# tactile.net
KiCad netlist of a schematic drawn in EAGLE
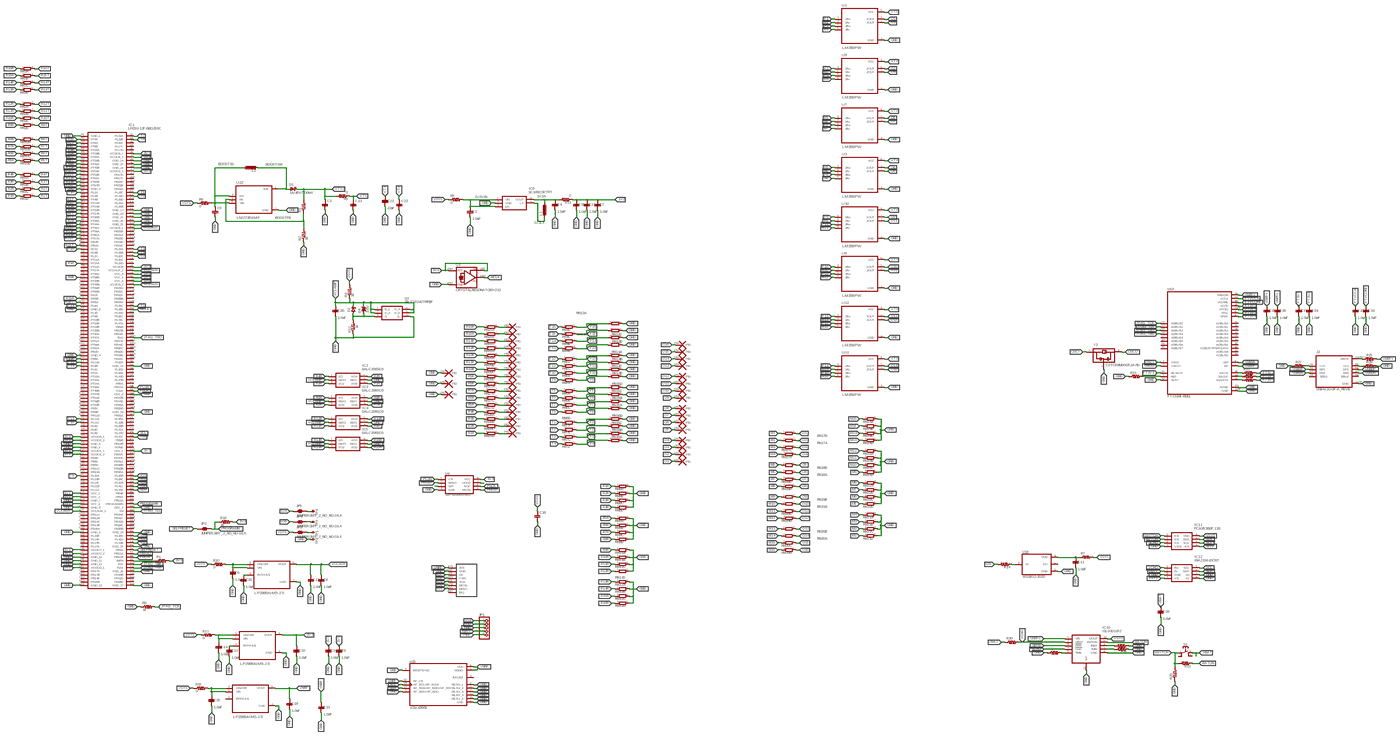
[diagram p0: schematic, sheet 1, overview]
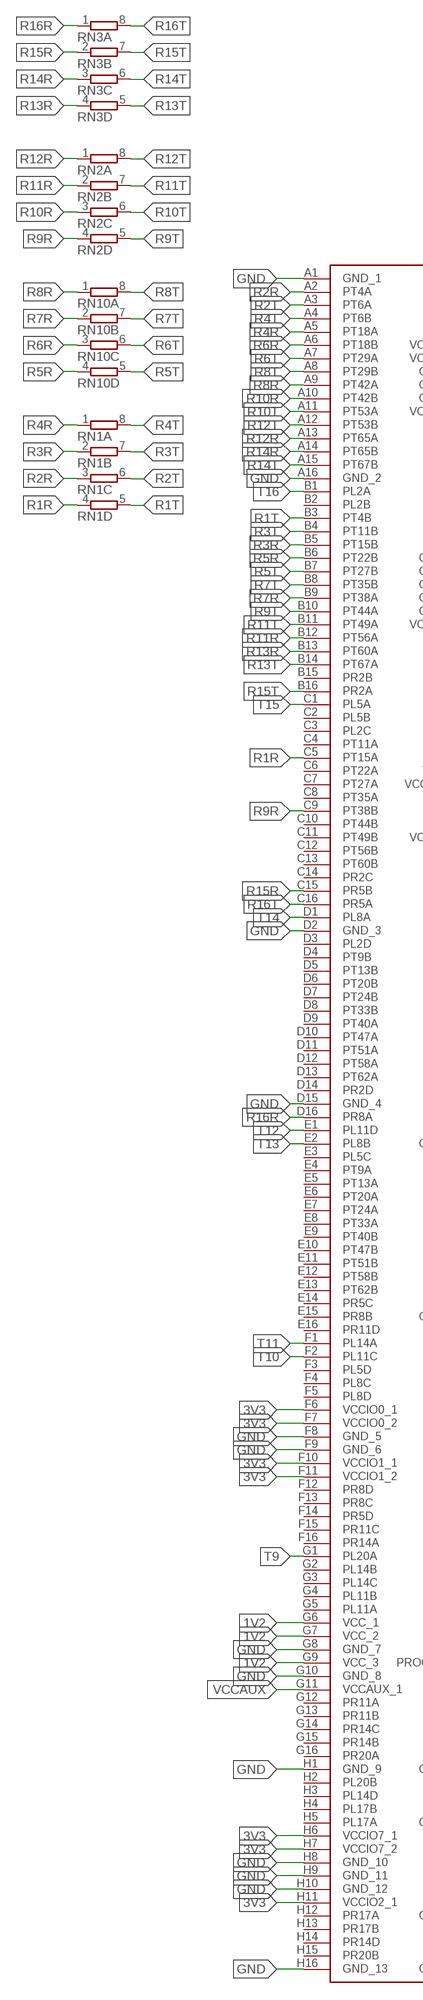
[diagram p1: schematic, sheet 1, part 1 of 4]
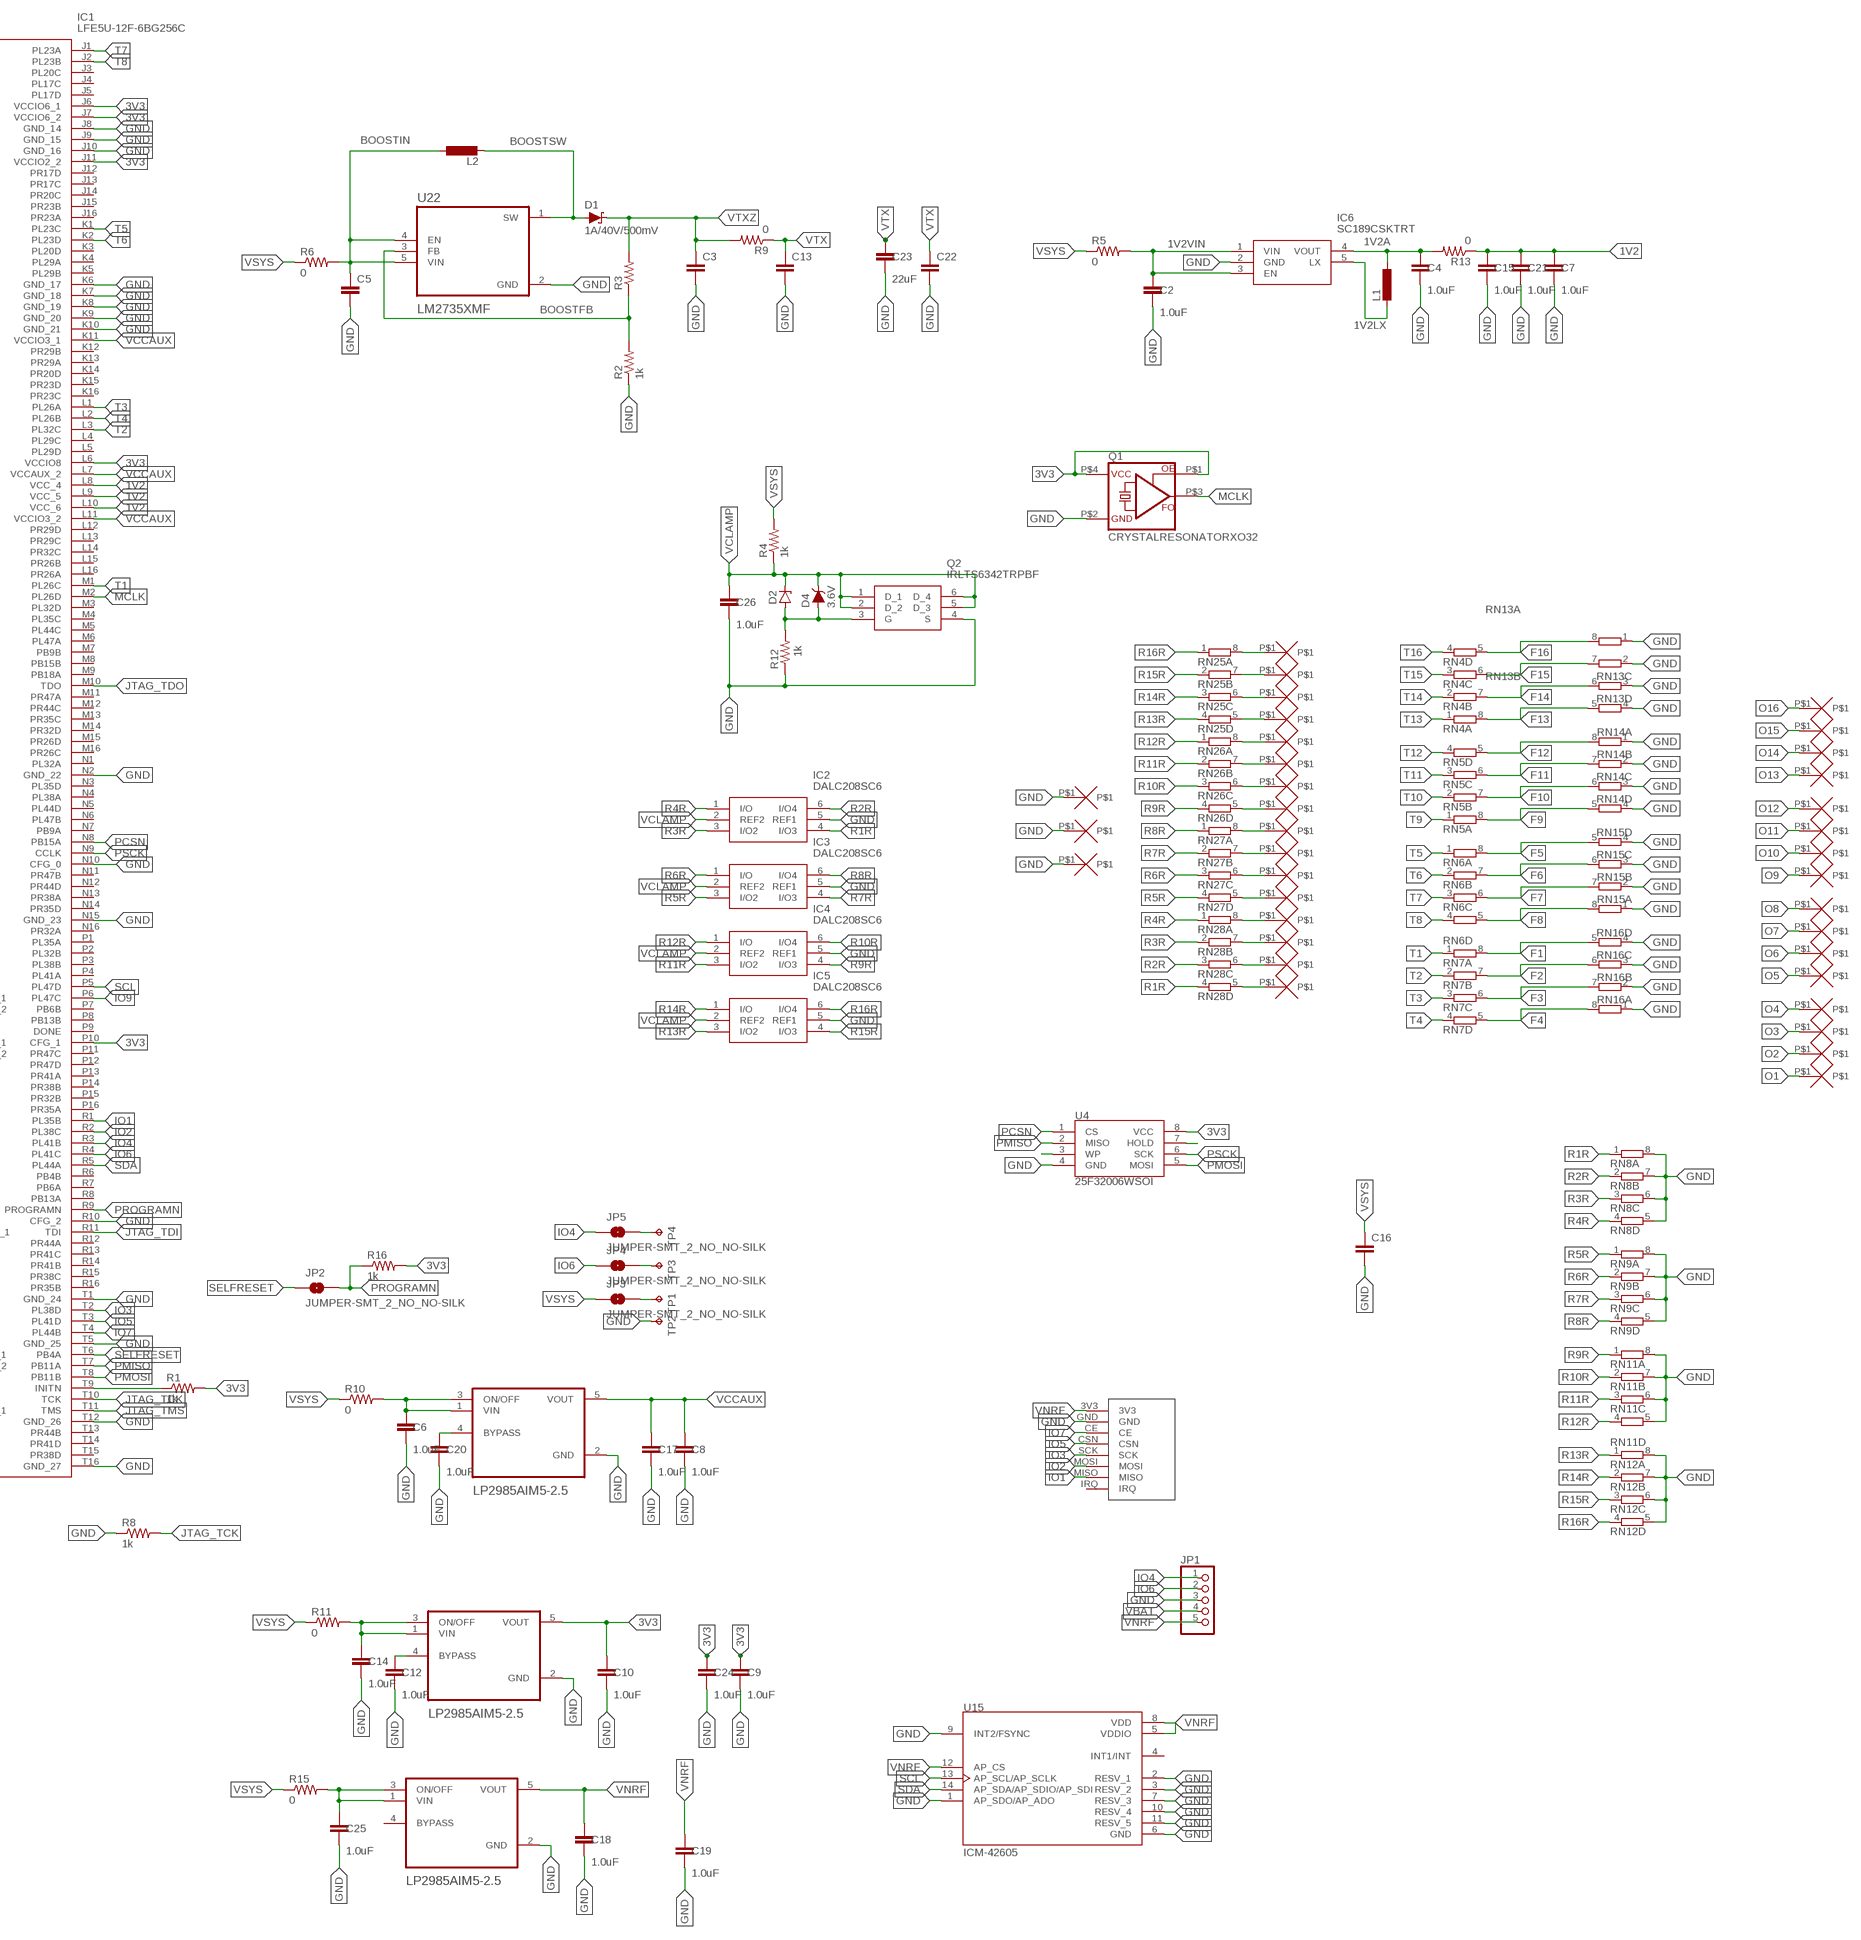
[diagram p2: schematic, sheet 1, part 2 of 4]
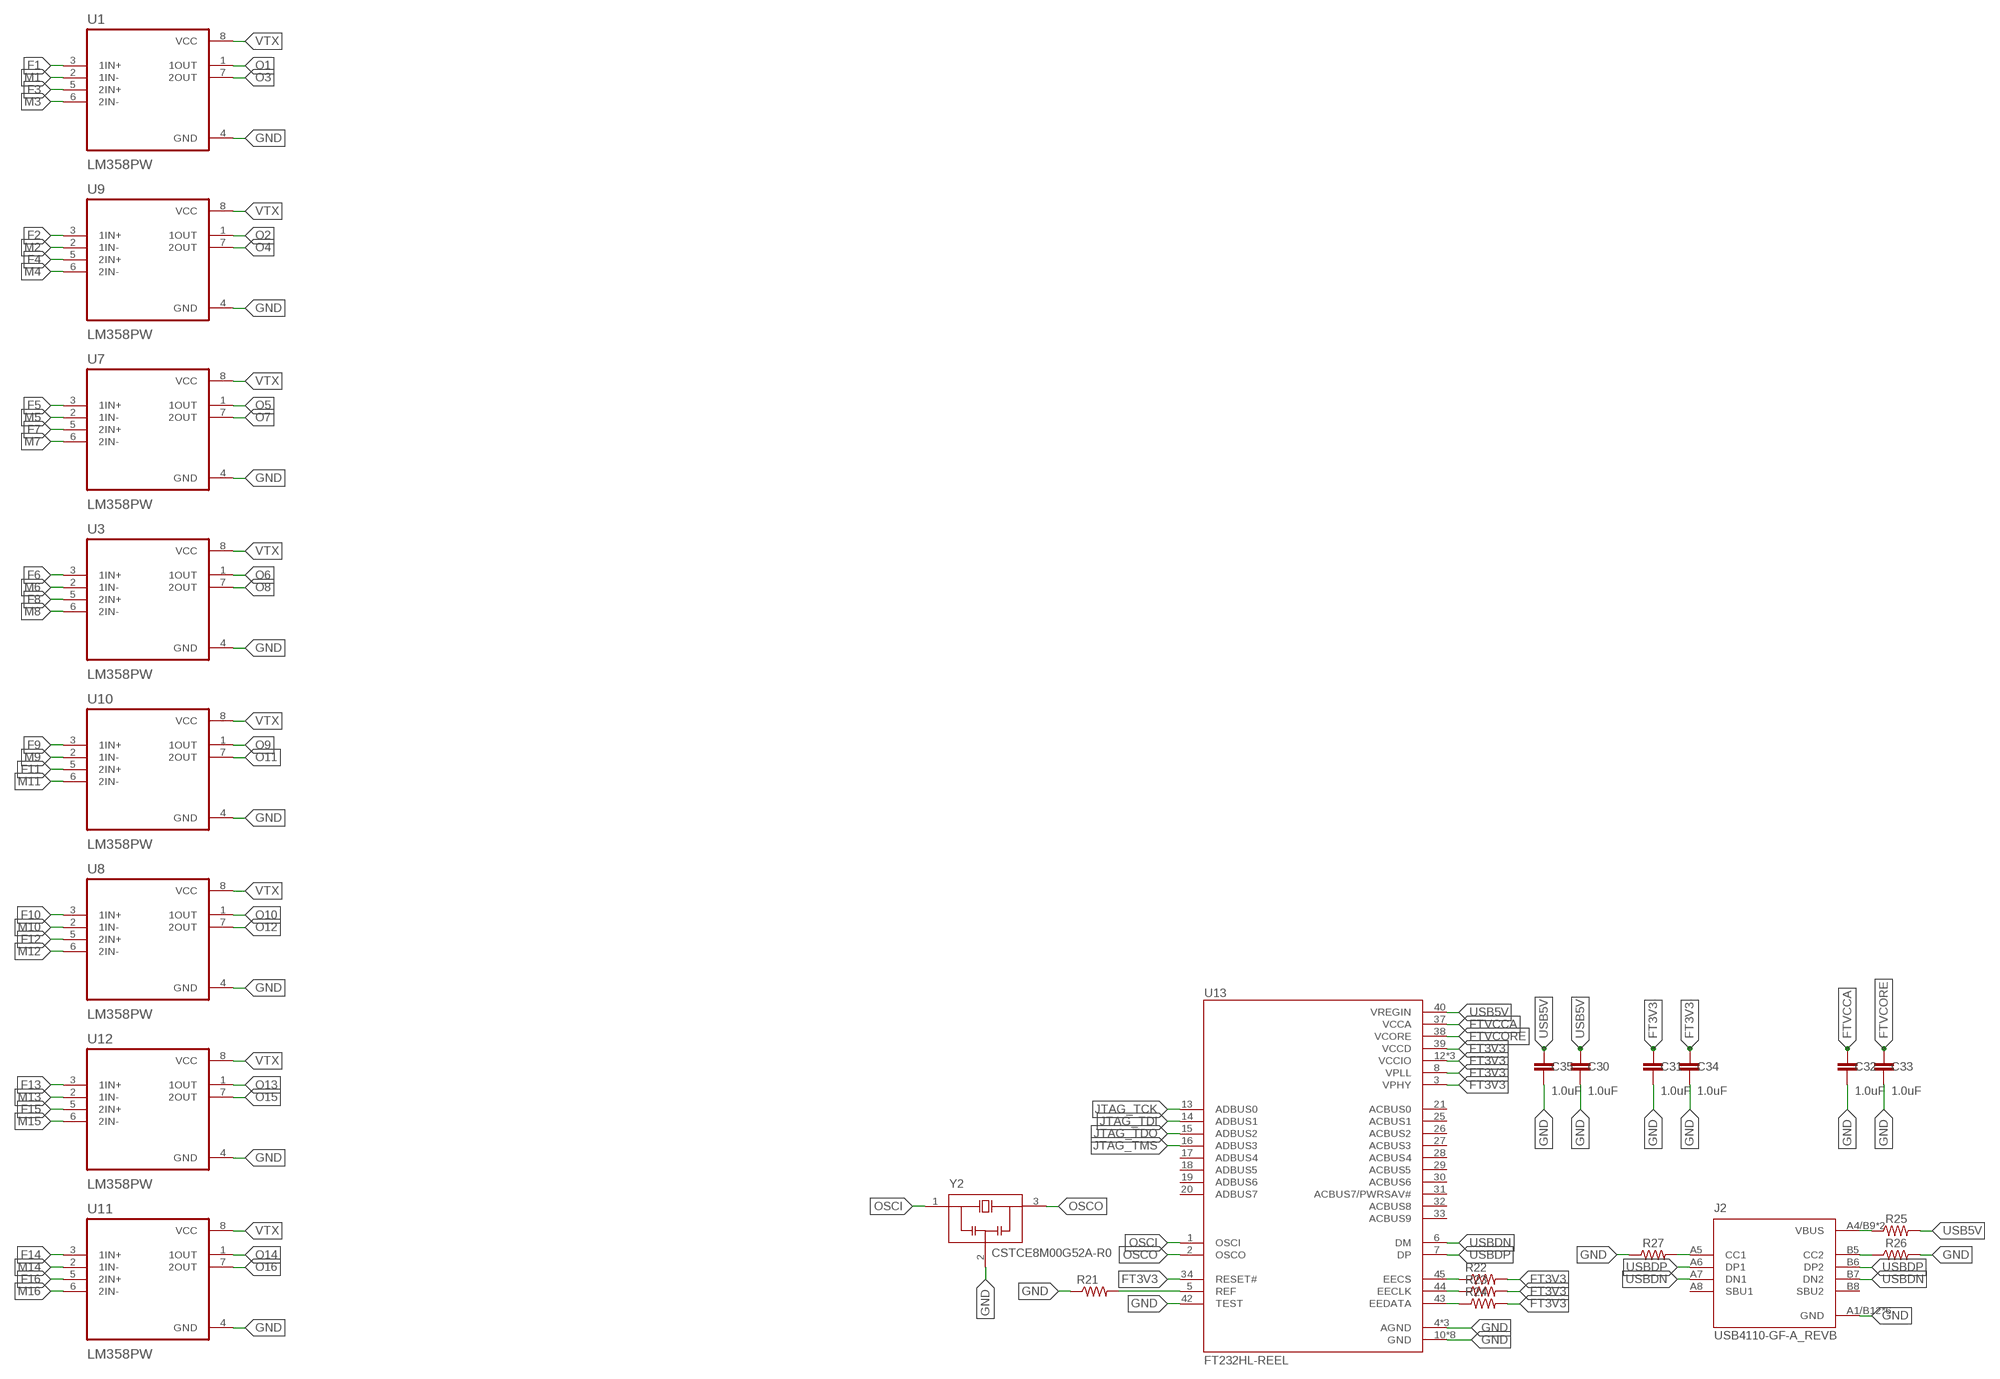
[diagram p3: schematic, sheet 1, part 3 of 4]
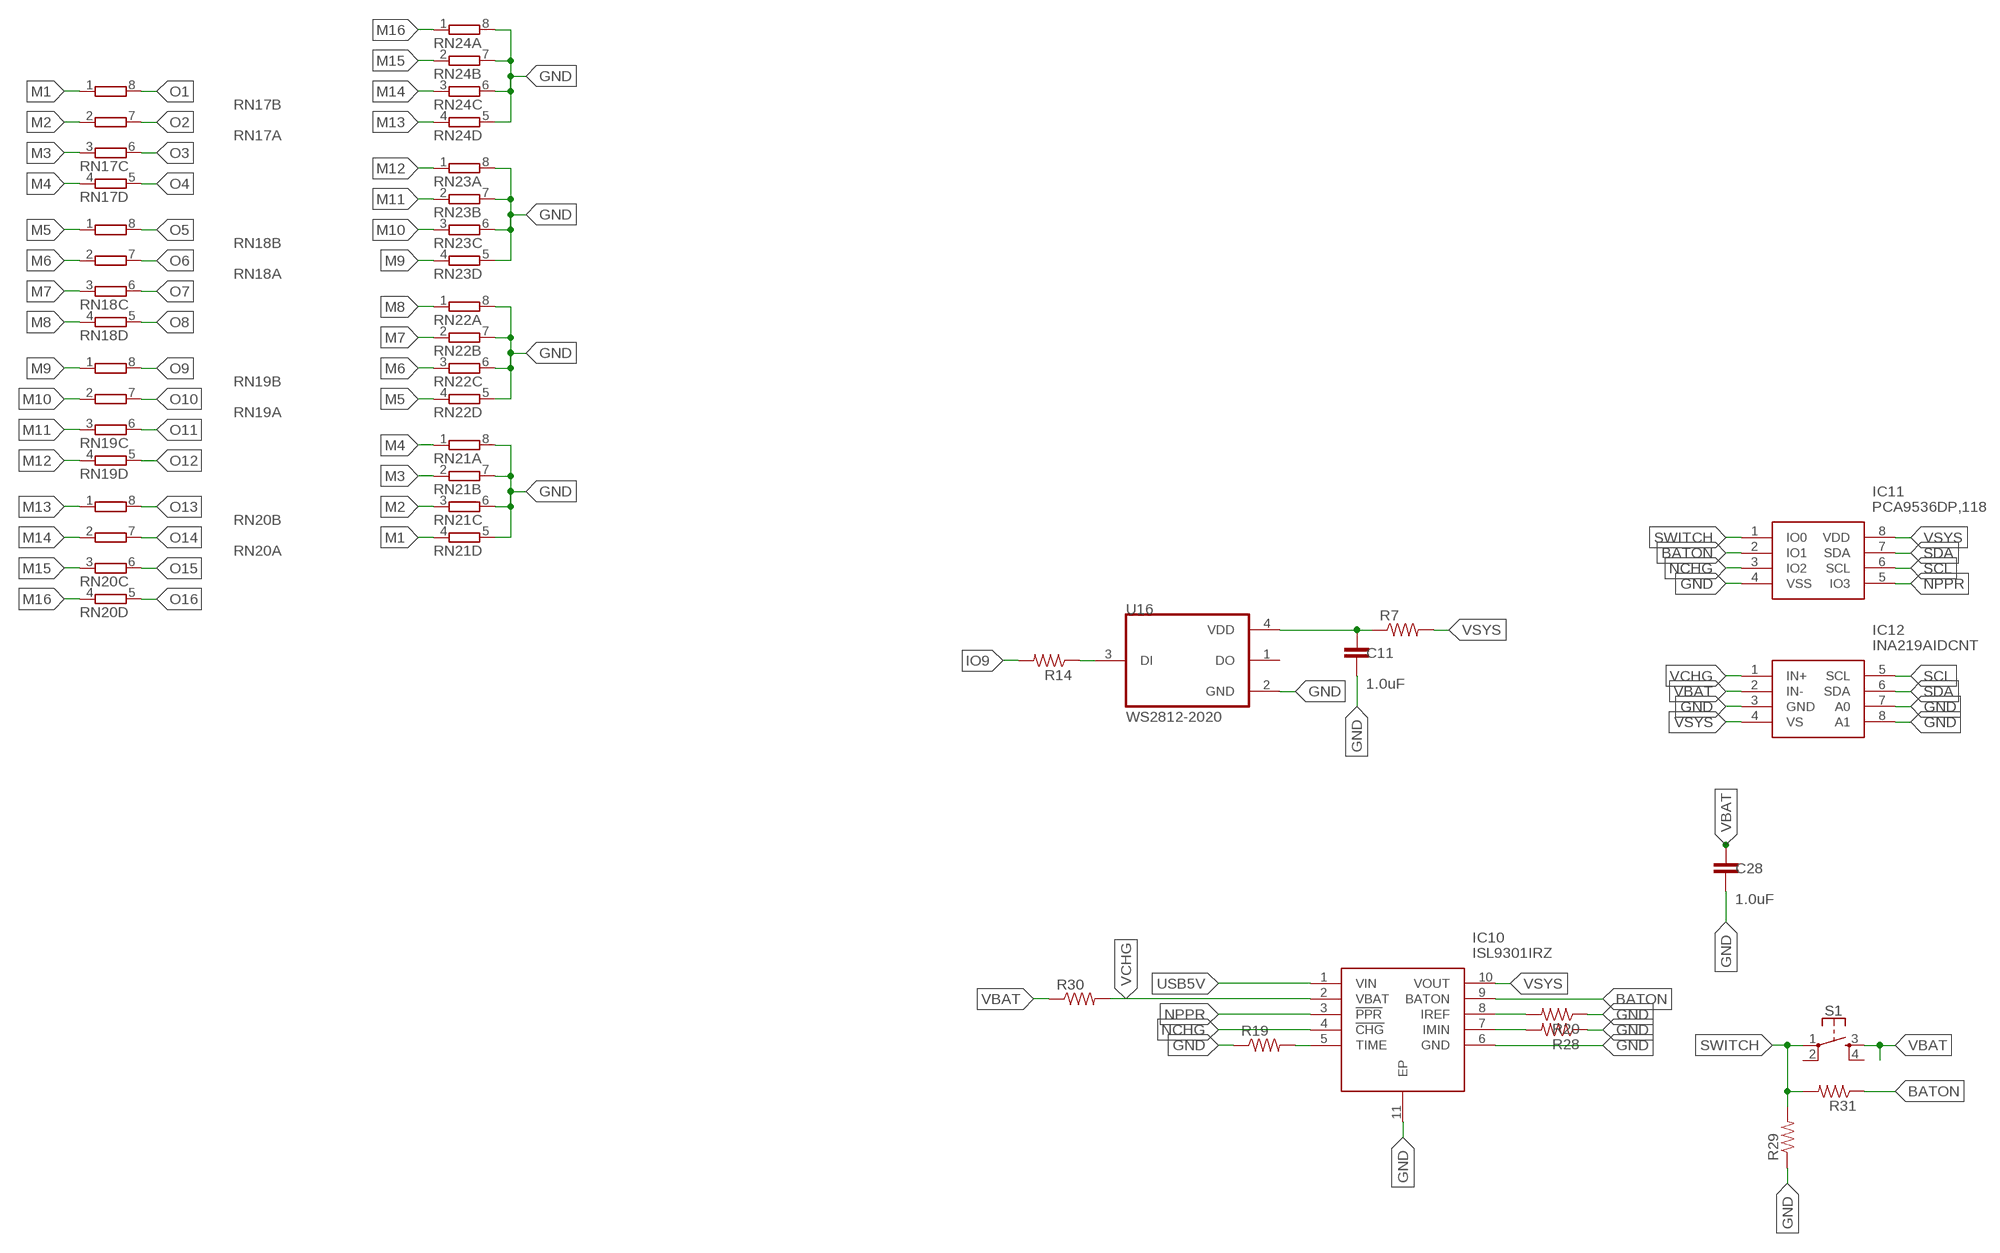
[diagram p4: schematic, sheet 1, part 4 of 4]

(export (version "E")
  (design (tool "Eeschema 10.0.6"))
  (components
    (comp (ref "C2")
      (value "1.0uF")
      (footprint "eagle-import:0603")
      (libsource (lib "eagle-import") (part "1.0UF-0603-16V-10%"))
    )
    (comp (ref "C3")
      (value "C-EUC0805")
      (footprint "eagle-import:C0805")
      (libsource (lib "eagle-import") (part "C-EUC0805"))
    )
    (comp (ref "C4")
      (value "1.0uF")
      (footprint "eagle-import:0603")
      (libsource (lib "eagle-import") (part "1.0UF-0603-16V-10%"))
    )
    (comp (ref "C5")
      (value "C-EUC0805")
      (footprint "eagle-import:C0805")
      (libsource (lib "eagle-import") (part "C-EUC0805"))
    )
    (comp (ref "C6")
      (value "1.0uF")
      (footprint "eagle-import:0603")
      (libsource (lib "eagle-import") (part "1.0UF-0603-16V-10%"))
    )
    (comp (ref "C7")
      (value "1.0uF")
      (footprint "eagle-import:0603")
      (libsource (lib "eagle-import") (part "1.0UF-0603-16V-10%"))
    )
    (comp (ref "C8")
      (value "1.0uF")
      (footprint "eagle-import:0603")
      (libsource (lib "eagle-import") (part "1.0UF-0603-16V-10%"))
    )
    (comp (ref "C9")
      (value "1.0uF")
      (footprint "eagle-import:0603")
      (libsource (lib "eagle-import") (part "1.0UF-0603-16V-10%"))
    )
    (comp (ref "C10")
      (value "1.0uF")
      (footprint "eagle-import:0603")
      (libsource (lib "eagle-import") (part "1.0UF-0603-16V-10%"))
    )
    (comp (ref "C11")
      (value "1.0uF")
      (footprint "eagle-import:0603")
      (libsource (lib "eagle-import") (part "1.0UF-0603-16V-10%"))
    )
    (comp (ref "C12")
      (value "1.0uF")
      (footprint "eagle-import:0603")
      (libsource (lib "eagle-import") (part "1.0UF-0603-16V-10%"))
    )
    (comp (ref "C13")
      (value "C-EUC0805")
      (footprint "eagle-import:C0805")
      (libsource (lib "eagle-import") (part "C-EUC0805"))
    )
    (comp (ref "C14")
      (value "1.0uF")
      (footprint "eagle-import:0603")
      (libsource (lib "eagle-import") (part "1.0UF-0603-16V-10%"))
    )
    (comp (ref "C15")
      (value "1.0uF")
      (footprint "eagle-import:0603")
      (libsource (lib "eagle-import") (part "1.0UF-0603-16V-10%"))
    )
    (comp (ref "C16")
      (value "C-EUC1812")
      (footprint "eagle-import:C1812")
      (libsource (lib "eagle-import") (part "C-EUC1812"))
    )
    (comp (ref "C17")
      (value "1.0uF")
      (footprint "eagle-import:0603")
      (libsource (lib "eagle-import") (part "1.0UF-0603-16V-10%"))
    )
    (comp (ref "C18")
      (value "1.0uF")
      (footprint "eagle-import:0603")
      (libsource (lib "eagle-import") (part "1.0UF-0603-16V-10%"))
    )
    (comp (ref "C19")
      (value "1.0uF")
      (footprint "eagle-import:0603")
      (libsource (lib "eagle-import") (part "1.0UF-0603-16V-10%"))
    )
    (comp (ref "C20")
      (value "1.0uF")
      (footprint "eagle-import:0603")
      (libsource (lib "eagle-import") (part "1.0UF-0603-16V-10%"))
    )
    (comp (ref "C21")
      (value "1.0uF")
      (footprint "eagle-import:0603")
      (libsource (lib "eagle-import") (part "1.0UF-0603-16V-10%"))
    )
    (comp (ref "C22")
      (value "C-EUC0805")
      (footprint "eagle-import:C0805")
      (libsource (lib "eagle-import") (part "C-EUC0805"))
    )
    (comp (ref "C23")
      (value "22uF")
      (footprint "eagle-import:0805")
      (libsource (lib "eagle-import") (part "22UF-0805-16V-20%"))
    )
    (comp (ref "C24")
      (value "1.0uF")
      (footprint "eagle-import:0603")
      (libsource (lib "eagle-import") (part "1.0UF-0603-16V-10%"))
    )
    (comp (ref "C25")
      (value "1.0uF")
      (footprint "eagle-import:0603")
      (libsource (lib "eagle-import") (part "1.0UF-0603-16V-10%"))
    )
    (comp (ref "C26")
      (value "1.0uF")
      (footprint "eagle-import:0603")
      (libsource (lib "eagle-import") (part "1.0UF-0603-16V-10%"))
    )
    (comp (ref "C28")
      (value "1.0uF")
      (footprint "eagle-import:0603")
      (libsource (lib "eagle-import") (part "1.0UF-0603-16V-10%"))
    )
    (comp (ref "C30")
      (value "1.0uF")
      (footprint "eagle-import:1206")
      (libsource (lib "eagle-import") (part "1.0UF-1206-50V-10%"))
    )
    (comp (ref "C31")
      (value "1.0uF")
      (footprint "eagle-import:0603")
      (libsource (lib "eagle-import") (part "1.0UF-0603-16V-10%"))
    )
    (comp (ref "C32")
      (value "1.0uF")
      (footprint "eagle-import:0603")
      (libsource (lib "eagle-import") (part "1.0UF-0603-16V-10%"))
    )
    (comp (ref "C33")
      (value "1.0uF")
      (footprint "eagle-import:0603")
      (libsource (lib "eagle-import") (part "1.0UF-0603-16V-10%"))
    )
    (comp (ref "C34")
      (value "1.0uF")
      (footprint "eagle-import:0603")
      (libsource (lib "eagle-import") (part "1.0UF-0603-16V-10%"))
    )
    (comp (ref "C35")
      (value "1.0uF")
      (footprint "eagle-import:0603")
      (libsource (lib "eagle-import") (part "1.0UF-0603-16V-10%"))
    )
    (comp (ref "D1")
      (value "1A/40V/500mV")
      (footprint "eagle-import:SMA-DIODE")
      (libsource (lib "eagle-import") (part "DIODE-SCHOTTKY-SS14"))
    )
    (comp (ref "D2")
      (value "ZENER-DIODESOT23")
      (footprint "eagle-import:SOT23")
      (libsource (lib "eagle-import") (part "ZENER-DIODESOT23"))
    )
    (comp (ref "D4")
      (value "3.6V")
      (footprint "eagle-import:SOD-323")
      (libsource (lib "eagle-import") (part "DIODE-ZENER-BZT52C3V6S"))
    )
    (comp (ref "IC1")
      (value "LFE5U-12F-6BG256C")
      (footprint "eagle-import:BGA256C80P16X16_1400X1400X170")
      (fields (field (name "MF") "Lattice Semiconductor"))
      (libsource (lib "eagle-import") (part "LFE5U-12F-6BG256C"))
    )
    (comp (ref "IC2")
      (value "DALC208SC6")
      (footprint "eagle-import:SOT95P280X145-6N")
      (fields (field (name "MF") "STMicroelectronics"))
      (libsource (lib "eagle-import") (part "DALC208SC6"))
    )
    (comp (ref "IC3")
      (value "DALC208SC6")
      (footprint "eagle-import:SOT95P280X145-6N")
      (fields (field (name "MF") "STMicroelectronics"))
      (libsource (lib "eagle-import") (part "DALC208SC6"))
    )
    (comp (ref "IC4")
      (value "DALC208SC6")
      (footprint "eagle-import:SOT95P280X145-6N")
      (fields (field (name "MF") "STMicroelectronics"))
      (libsource (lib "eagle-import") (part "DALC208SC6"))
    )
    (comp (ref "IC5")
      (value "DALC208SC6")
      (footprint "eagle-import:SOT95P280X145-6N")
      (fields (field (name "MF") "STMicroelectronics"))
      (libsource (lib "eagle-import") (part "DALC208SC6"))
    )
    (comp (ref "IC6")
      (value "SC189CSKTRT")
      (footprint "eagle-import:SOT95P280X145-5N")
      (fields (field (name "MOUSER_PART_NUMBER") "947-SC189CSKTRT"))
      (libsource (lib "eagle-import") (part "SC189CSKTRT"))
    )
    (comp (ref "IC10")
      (value "ISL9301IRZ")
      (footprint "eagle-import:SON50P300X300X90-11N")
      (fields (field (name "MOUSER_PART_NUMBER") "968-ISL9301IRZ"))
      (libsource (lib "eagle-import") (part "ISL9301IRZ"))
    )
    (comp (ref "IC11")
      (value "PCA9536DP,118")
      (footprint "eagle-import:SOP65P490X110-8N")
      (fields (field (name "MOUSER_PART_NUMBER") "771-PCA9536DP-T"))
      (libsource (lib "eagle-import") (part "PCA9536DP,118"))
    )
    (comp (ref "IC12")
      (value "INA219AIDCNT")
      (footprint "eagle-import:SOT65P280X145-8N")
      (fields (field (name "MOUSER_PART_NUMBER") "595-INA219AIDCNT"))
      (libsource (lib "eagle-import") (part "INA219AIDCNT"))
    )
    (comp (ref "J2")
      (value "USB4110-GF-A_REVB")
      (footprint "eagle-import:GCT_USB4110-GF-A_REVB")
      (fields (field (name "MF") "GCT") (field (name "MP") "USB4110-GF-A"))
      (libsource (lib "eagle-import") (part "USB4110-GF-A_REVB"))
    )
    (comp (ref "JP1")
      (value "PINHD-1X5M")
      (footprint "eagle-import:1X05M")
      (libsource (lib "eagle-import") (part "PINHD-1X5M"))
    )
    (comp (ref "JP2")
      (value "JUMPER-SMT_2_NO_NO-SILK")
      (footprint "eagle-import:SMT-JUMPER_2_NO_NO-SILK")
      (libsource (lib "eagle-import") (part "JUMPER-SMT_2_NO_NO-SILK"))
    )
    (comp (ref "JP3")
      (value "JUMPER-SMT_2_NO_NO-SILK")
      (footprint "eagle-import:SMT-JUMPER_2_NO_NO-SILK")
      (libsource (lib "eagle-import") (part "JUMPER-SMT_2_NO_NO-SILK"))
    )
    (comp (ref "JP4")
      (value "JUMPER-SMT_2_NO_NO-SILK")
      (footprint "eagle-import:SMT-JUMPER_2_NO_NO-SILK")
      (libsource (lib "eagle-import") (part "JUMPER-SMT_2_NO_NO-SILK"))
    )
    (comp (ref "JP5")
      (value "JUMPER-SMT_2_NO_NO-SILK")
      (footprint "eagle-import:SMT-JUMPER_2_NO_NO-SILK")
      (libsource (lib "eagle-import") (part "JUMPER-SMT_2_NO_NO-SILK"))
    )
    (comp (ref "L1")
      (value "L-EUL3230M")
      (footprint "eagle-import:L3230M")
      (libsource (lib "eagle-import") (part "L-EUL3230M"))
    )
    (comp (ref "L2")
      (value "L-EUL3225P")
      (footprint "eagle-import:L3225P")
      (libsource (lib "eagle-import") (part "L-EUL3225P"))
    )
    (comp (ref "Q1")
      (value "CRYSTALRESONATORXO32")
      (footprint "eagle-import:XO32")
      (libsource (lib "eagle-import") (part "CRYSTALRESONATORXO32"))
    )
    (comp (ref "Q2")
      (value "IRLTS6342TRPBF")
      (footprint "eagle-import:SOT95P280X145-6N")
      (fields (field (name "MOUSER_PART_NUMBER") "942-IRLTS6342TRPBF"))
      (libsource (lib "eagle-import") (part "IRLTS6342TRPBF"))
    )
    (comp (ref "R1")
      (value "1k")
      (footprint "eagle-import:0603")
      (libsource (lib "eagle-import") (part "1KOHM-0603-1/10W-1%"))
    )
    (comp (ref "R2")
      (value "1k")
      (footprint "eagle-import:0603")
      (libsource (lib "eagle-import") (part "1KOHM-0603-1/10W-1%"))
    )
    (comp (ref "R3")
      (value "1k")
      (footprint "eagle-import:0603")
      (libsource (lib "eagle-import") (part "1KOHM-0603-1/10W-1%"))
    )
    (comp (ref "R4")
      (value "1k")
      (footprint "eagle-import:0603")
      (libsource (lib "eagle-import") (part "1KOHM-0603-1/10W-1%"))
    )
    (comp (ref "R5")
      (value "0")
      (footprint "eagle-import:0603")
      (libsource (lib "eagle-import") (part "0OHM-0603-1/10W"))
    )
    (comp (ref "R6")
      (value "0")
      (footprint "eagle-import:0603")
      (libsource (lib "eagle-import") (part "0OHM-0603-1/10W"))
    )
    (comp (ref "R7")
      (value "RESISTOR0603")
      (footprint "eagle-import:0603")
      (libsource (lib "eagle-import") (part "RESISTOR0603"))
    )
    (comp (ref "R8")
      (value "1k")
      (footprint "eagle-import:0603")
      (libsource (lib "eagle-import") (part "1KOHM-0603-1/10W-1%"))
    )
    (comp (ref "R9")
      (value "0")
      (footprint "eagle-import:0603")
      (libsource (lib "eagle-import") (part "0OHM-0603-1/10W"))
    )
    (comp (ref "R10")
      (value "0")
      (footprint "eagle-import:0603")
      (libsource (lib "eagle-import") (part "0OHM-0603-1/10W"))
    )
    (comp (ref "R11")
      (value "0")
      (footprint "eagle-import:0603")
      (libsource (lib "eagle-import") (part "0OHM-0603-1/10W"))
    )
    (comp (ref "R12")
      (value "1k")
      (footprint "eagle-import:0603")
      (libsource (lib "eagle-import") (part "1KOHM-0603-1/10W-1%"))
    )
    (comp (ref "R13")
      (value "0")
      (footprint "eagle-import:0603")
      (libsource (lib "eagle-import") (part "0OHM-0603-1/10W"))
    )
    (comp (ref "R14")
      (value "RESISTOR0603")
      (footprint "eagle-import:0603")
      (libsource (lib "eagle-import") (part "RESISTOR0603"))
    )
    (comp (ref "R15")
      (value "0")
      (footprint "eagle-import:0603")
      (libsource (lib "eagle-import") (part "0OHM-0603-1/10W"))
    )
    (comp (ref "R16")
      (value "1k")
      (footprint "eagle-import:0603")
      (libsource (lib "eagle-import") (part "1KOHM-0603-1/10W-1%"))
    )
    (comp (ref "R19")
      (value "RESISTOR0603")
      (footprint "eagle-import:0603")
      (libsource (lib "eagle-import") (part "RESISTOR0603"))
    )
    (comp (ref "R20")
      (value "RESISTOR0603")
      (footprint "eagle-import:0603")
      (libsource (lib "eagle-import") (part "RESISTOR0603"))
    )
    (comp (ref "R21")
      (value "RESISTOR0603")
      (footprint "eagle-import:0603")
      (libsource (lib "eagle-import") (part "RESISTOR0603"))
    )
    (comp (ref "R22")
      (value "RESISTOR0603")
      (footprint "eagle-import:0603")
      (libsource (lib "eagle-import") (part "RESISTOR0603"))
    )
    (comp (ref "R23")
      (value "RESISTOR0603")
      (footprint "eagle-import:0603")
      (libsource (lib "eagle-import") (part "RESISTOR0603"))
    )
    (comp (ref "R24")
      (value "RESISTOR0603")
      (footprint "eagle-import:0603")
      (libsource (lib "eagle-import") (part "RESISTOR0603"))
    )
    (comp (ref "R25")
      (value "RESISTOR0603")
      (footprint "eagle-import:0603")
      (libsource (lib "eagle-import") (part "RESISTOR0603"))
    )
    (comp (ref "R26")
      (value "RESISTOR0603")
      (footprint "eagle-import:0603")
      (libsource (lib "eagle-import") (part "RESISTOR0603"))
    )
    (comp (ref "R27")
      (value "RESISTOR0603")
      (footprint "eagle-import:0603")
      (libsource (lib "eagle-import") (part "RESISTOR0603"))
    )
    (comp (ref "R28")
      (value "RESISTOR0603")
      (footprint "eagle-import:0603")
      (libsource (lib "eagle-import") (part "RESISTOR0603"))
    )
    (comp (ref "R29")
      (value "RESISTOR0603")
      (footprint "eagle-import:0603")
      (libsource (lib "eagle-import") (part "RESISTOR0603"))
    )
    (comp (ref "R30")
      (value "RESISTOR0603")
      (footprint "eagle-import:0603")
      (libsource (lib "eagle-import") (part "RESISTOR0603"))
    )
    (comp (ref "R31")
      (value "RESISTOR0603")
      (footprint "eagle-import:0603")
      (libsource (lib "eagle-import") (part "RESISTOR0603"))
    )
    (comp (ref "RN1")
      (value "4R-NEXBV8V")
      (footprint "eagle-import:EXBV8V")
      (libsource (lib "eagle-import") (part "4R-NEXBV8V"))
    )
    (comp (ref "RN2")
      (value "4R-NEXBV8V")
      (footprint "eagle-import:EXBV8V")
      (libsource (lib "eagle-import") (part "4R-NEXBV8V"))
    )
    (comp (ref "RN3")
      (value "4R-NEXBV8V")
      (footprint "eagle-import:EXBV8V")
      (libsource (lib "eagle-import") (part "4R-NEXBV8V"))
    )
    (comp (ref "RN4")
      (value "4R-NEXBV8V")
      (footprint "eagle-import:EXBV8V")
      (libsource (lib "eagle-import") (part "4R-NEXBV8V"))
    )
    (comp (ref "RN5")
      (value "4R-NEXBV8V")
      (footprint "eagle-import:EXBV8V")
      (libsource (lib "eagle-import") (part "4R-NEXBV8V"))
    )
    (comp (ref "RN6")
      (value "4R-NEXBV8V")
      (footprint "eagle-import:EXBV8V")
      (libsource (lib "eagle-import") (part "4R-NEXBV8V"))
    )
    (comp (ref "RN7")
      (value "4R-NEXBV8V")
      (footprint "eagle-import:EXBV8V")
      (libsource (lib "eagle-import") (part "4R-NEXBV8V"))
    )
    (comp (ref "RN8")
      (value "4R-NEXBV8V")
      (footprint "eagle-import:EXBV8V")
      (libsource (lib "eagle-import") (part "4R-NEXBV8V"))
    )
    (comp (ref "RN9")
      (value "4R-NEXBV8V")
      (footprint "eagle-import:EXBV8V")
      (libsource (lib "eagle-import") (part "4R-NEXBV8V"))
    )
    (comp (ref "RN10")
      (value "4R-NEXBV8V")
      (footprint "eagle-import:EXBV8V")
      (libsource (lib "eagle-import") (part "4R-NEXBV8V"))
    )
    (comp (ref "RN11")
      (value "4R-NEXBV8V")
      (footprint "eagle-import:EXBV8V")
      (libsource (lib "eagle-import") (part "4R-NEXBV8V"))
    )
    (comp (ref "RN12")
      (value "4R-NEXBV8V")
      (footprint "eagle-import:EXBV8V")
      (libsource (lib "eagle-import") (part "4R-NEXBV8V"))
    )
    (comp (ref "RN13")
      (value "4R-NEXBV8V")
      (footprint "eagle-import:EXBV8V")
      (libsource (lib "eagle-import") (part "4R-NEXBV8V"))
    )
    (comp (ref "RN14")
      (value "4R-NEXBV8V")
      (footprint "eagle-import:EXBV8V")
      (libsource (lib "eagle-import") (part "4R-NEXBV8V"))
    )
    (comp (ref "RN15")
      (value "4R-NEXBV8V")
      (footprint "eagle-import:EXBV8V")
      (libsource (lib "eagle-import") (part "4R-NEXBV8V"))
    )
    (comp (ref "RN16")
      (value "4R-NEXBV8V")
      (footprint "eagle-import:EXBV8V")
      (libsource (lib "eagle-import") (part "4R-NEXBV8V"))
    )
    (comp (ref "RN17")
      (value "4R-NEXBV8V")
      (footprint "eagle-import:EXBV8V")
      (libsource (lib "eagle-import") (part "4R-NEXBV8V"))
    )
    (comp (ref "RN18")
      (value "4R-NEXBV8V")
      (footprint "eagle-import:EXBV8V")
      (libsource (lib "eagle-import") (part "4R-NEXBV8V"))
    )
    (comp (ref "RN19")
      (value "4R-NEXBV8V")
      (footprint "eagle-import:EXBV8V")
      (libsource (lib "eagle-import") (part "4R-NEXBV8V"))
    )
    (comp (ref "RN20")
      (value "4R-NEXBV8V")
      (footprint "eagle-import:EXBV8V")
      (libsource (lib "eagle-import") (part "4R-NEXBV8V"))
    )
    (comp (ref "RN21")
      (value "4R-NEXBV8V")
      (footprint "eagle-import:EXBV8V")
      (libsource (lib "eagle-import") (part "4R-NEXBV8V"))
    )
    (comp (ref "RN22")
      (value "4R-NEXBV8V")
      (footprint "eagle-import:EXBV8V")
      (libsource (lib "eagle-import") (part "4R-NEXBV8V"))
    )
    (comp (ref "RN23")
      (value "4R-NEXBV8V")
      (footprint "eagle-import:EXBV8V")
      (libsource (lib "eagle-import") (part "4R-NEXBV8V"))
    )
    (comp (ref "RN24")
      (value "4R-NEXBV8V")
      (footprint "eagle-import:EXBV8V")
      (libsource (lib "eagle-import") (part "4R-NEXBV8V"))
    )
    (comp (ref "RN25")
      (value "4R-NEXBV8V")
      (footprint "eagle-import:EXBV8V")
      (libsource (lib "eagle-import") (part "4R-NEXBV8V"))
    )
    (comp (ref "RN26")
      (value "4R-NEXBV8V")
      (footprint "eagle-import:EXBV8V")
      (libsource (lib "eagle-import") (part "4R-NEXBV8V"))
    )
    (comp (ref "RN27")
      (value "4R-NEXBV8V")
      (footprint "eagle-import:EXBV8V")
      (libsource (lib "eagle-import") (part "4R-NEXBV8V"))
    )
    (comp (ref "RN28")
      (value "4R-NEXBV8V")
      (footprint "eagle-import:EXBV8V")
      (libsource (lib "eagle-import") (part "4R-NEXBV8V"))
    )
    (comp (ref "S1")
      (value "MOMENTARY-SWITCH-SPST-2-SMD-5.2MM")
      (footprint "eagle-import:TACTILE_SWITCH_SMD_5.2MM")
      (libsource (lib "eagle-import") (part "MOMENTARY-SWITCH-SPST-2-SMD-5.2MM"))
    )
    (comp (ref "TP1")
      (value "TPTP12SQ")
      (footprint "eagle-import:TP12SQ")
      (libsource (lib "eagle-import") (part "TPTP12SQ"))
    )
    (comp (ref "TP2")
      (value "TPTP12SQ")
      (footprint "eagle-import:TP12SQ")
      (libsource (lib "eagle-import") (part "TPTP12SQ"))
    )
    (comp (ref "TP3")
      (value "TPTP12SQ")
      (footprint "eagle-import:TP12SQ")
      (libsource (lib "eagle-import") (part "TPTP12SQ"))
    )
    (comp (ref "TP4")
      (value "TPTP12SQ")
      (footprint "eagle-import:TP12SQ")
      (libsource (lib "eagle-import") (part "TPTP12SQ"))
    )
    (comp (ref "U$1")
      (value "PADPAD3X05")
      (footprint "eagle-import:PAD3X05")
      (libsource (lib "eagle-import") (part "PADPAD3X05"))
    )
    (comp (ref "U$2")
      (value "PADPAD3X05")
      (footprint "eagle-import:PAD3X05")
      (libsource (lib "eagle-import") (part "PADPAD3X05"))
    )
    (comp (ref "U$3")
      (value "PADPAD3X05")
      (footprint "eagle-import:PAD3X05")
      (libsource (lib "eagle-import") (part "PADPAD3X05"))
    )
    (comp (ref "U$4")
      (value "PADPAD3X05")
      (footprint "eagle-import:PAD3X05")
      (libsource (lib "eagle-import") (part "PADPAD3X05"))
    )
    (comp (ref "U$5")
      (value "PADPAD3X05")
      (footprint "eagle-import:PAD3X05")
      (libsource (lib "eagle-import") (part "PADPAD3X05"))
    )
    (comp (ref "U$6")
      (value "PADPAD3X05")
      (footprint "eagle-import:PAD3X05")
      (libsource (lib "eagle-import") (part "PADPAD3X05"))
    )
    (comp (ref "U$7")
      (value "PADPAD3X05")
      (footprint "eagle-import:PAD3X05")
      (libsource (lib "eagle-import") (part "PADPAD3X05"))
    )
    (comp (ref "U$8")
      (value "PADPAD3X05")
      (footprint "eagle-import:PAD3X05")
      (libsource (lib "eagle-import") (part "PADPAD3X05"))
    )
    (comp (ref "U$9")
      (value "NRF24MODULE")
      (footprint "eagle-import:NRF24SMT")
      (libsource (lib "eagle-import") (part "NRF24MODULE"))
    )
    (comp (ref "U$10")
      (value "PADPAD3X05")
      (footprint "eagle-import:PAD3X05")
      (libsource (lib "eagle-import") (part "PADPAD3X05"))
    )
    (comp (ref "U$11")
      (value "PADPAD3X05")
      (footprint "eagle-import:PAD3X05")
      (libsource (lib "eagle-import") (part "PADPAD3X05"))
    )
    (comp (ref "U$12")
      (value "PADPAD3X05")
      (footprint "eagle-import:PAD3X05")
      (libsource (lib "eagle-import") (part "PADPAD3X05"))
    )
    (comp (ref "U$13")
      (value "PADPAD3X05")
      (footprint "eagle-import:PAD3X05")
      (libsource (lib "eagle-import") (part "PADPAD3X05"))
    )
    (comp (ref "U$14")
      (value "PADPAD3X05")
      (footprint "eagle-import:PAD3X05")
      (libsource (lib "eagle-import") (part "PADPAD3X05"))
    )
    (comp (ref "U$15")
      (value "PADPAD3X05")
      (footprint "eagle-import:PAD3X05")
      (libsource (lib "eagle-import") (part "PADPAD3X05"))
    )
    (comp (ref "U$16")
      (value "PADPAD3X05")
      (footprint "eagle-import:PAD3X05")
      (libsource (lib "eagle-import") (part "PADPAD3X05"))
    )
    (comp (ref "U$17")
      (value "PADPAD3X05")
      (footprint "eagle-import:PAD3X05")
      (libsource (lib "eagle-import") (part "PADPAD3X05"))
    )
    (comp (ref "U$18")
      (value "PADPAD3X05")
      (footprint "eagle-import:PAD3X05")
      (libsource (lib "eagle-import") (part "PADPAD3X05"))
    )
    (comp (ref "U$19")
      (value "PADPAD3X05")
      (footprint "eagle-import:PAD3X05")
      (libsource (lib "eagle-import") (part "PADPAD3X05"))
    )
    (comp (ref "U$20")
      (value "PADPAD3X05")
      (footprint "eagle-import:PAD3X05")
      (libsource (lib "eagle-import") (part "PADPAD3X05"))
    )
    (comp (ref "U$21")
      (value "PADPAD3X05")
      (footprint "eagle-import:PAD3X05")
      (libsource (lib "eagle-import") (part "PADPAD3X05"))
    )
    (comp (ref "U$22")
      (value "PADPAD3X05")
      (footprint "eagle-import:PAD3X05")
      (libsource (lib "eagle-import") (part "PADPAD3X05"))
    )
    (comp (ref "U$23")
      (value "PADPAD3X05")
      (footprint "eagle-import:PAD3X05")
      (libsource (lib "eagle-import") (part "PADPAD3X05"))
    )
    (comp (ref "U$24")
      (value "PADPAD3X05")
      (footprint "eagle-import:PAD3X05")
      (libsource (lib "eagle-import") (part "PADPAD3X05"))
    )
    (comp (ref "U$25")
      (value "PADPAD3X05")
      (footprint "eagle-import:PAD3X05")
      (libsource (lib "eagle-import") (part "PADPAD3X05"))
    )
    (comp (ref "U$26")
      (value "PADPAD3X05")
      (footprint "eagle-import:PAD3X05")
      (libsource (lib "eagle-import") (part "PADPAD3X05"))
    )
    (comp (ref "U$27")
      (value "PADPAD3X05")
      (footprint "eagle-import:PAD3X05")
      (libsource (lib "eagle-import") (part "PADPAD3X05"))
    )
    (comp (ref "U$28")
      (value "PADPAD3X05")
      (footprint "eagle-import:PAD3X05")
      (libsource (lib "eagle-import") (part "PADPAD3X05"))
    )
    (comp (ref "U$29")
      (value "PADPAD3X05")
      (footprint "eagle-import:PAD3X05")
      (libsource (lib "eagle-import") (part "PADPAD3X05"))
    )
    (comp (ref "U$30")
      (value "PADPAD3X05")
      (footprint "eagle-import:PAD3X05")
      (libsource (lib "eagle-import") (part "PADPAD3X05"))
    )
    (comp (ref "U$31")
      (value "PADPAD3X05")
      (footprint "eagle-import:PAD3X05")
      (libsource (lib "eagle-import") (part "PADPAD3X05"))
    )
    (comp (ref "U$32")
      (value "PADPAD3X05")
      (footprint "eagle-import:PAD3X05")
      (libsource (lib "eagle-import") (part "PADPAD3X05"))
    )
    (comp (ref "U$33")
      (value "PADPAD3X05")
      (footprint "eagle-import:PAD3X05")
      (libsource (lib "eagle-import") (part "PADPAD3X05"))
    )
    (comp (ref "U$34")
      (value "PADPAD3X05")
      (footprint "eagle-import:PAD3X05")
      (libsource (lib "eagle-import") (part "PADPAD3X05"))
    )
    (comp (ref "U$35")
      (value "PADPAD3X05")
      (footprint "eagle-import:PAD3X05")
      (libsource (lib "eagle-import") (part "PADPAD3X05"))
    )
    (comp (ref "U$36")
      (value "PADPAD3X05")
      (footprint "eagle-import:PAD3X05")
      (libsource (lib "eagle-import") (part "PADPAD3X05"))
    )
    (comp (ref "U1")
      (value "LM358PW")
      (footprint "eagle-import:SOP65P640X120-8N")
      (fields (field (name "MF") "Texas Instruments"))
      (libsource (lib "eagle-import") (part "LM358PW"))
    )
    (comp (ref "U3")
      (value "LM358PW")
      (footprint "eagle-import:SOP65P640X120-8N")
      (fields (field (name "MF") "Texas Instruments"))
      (libsource (lib "eagle-import") (part "LM358PW"))
    )
    (comp (ref "U4")
      (value "25F32006WSOI")
      (footprint "eagle-import:SO08-EIAJ")
      (libsource (lib "eagle-import") (part "SPI_FLASH-X25XXSMD1"))
    )
    (comp (ref "U5")
      (value "LP2985AIM5-2.5")
      (footprint "eagle-import:SOT95P280X145-5N")
      (fields (field (name "MF") "Texas Instruments") (field (name "MP") "LP2985AIM5-2.5/NOPB"))
      (libsource (lib "eagle-import") (part "LP2985AIM5-2.5"))
    )
    (comp (ref "U6")
      (value "LP2985AIM5-2.5")
      (footprint "eagle-import:SOT95P280X145-5N")
      (fields (field (name "MF") "Texas Instruments") (field (name "MP") "LP2985AIM5-2.5/NOPB"))
      (libsource (lib "eagle-import") (part "LP2985AIM5-2.5"))
    )
    (comp (ref "U7")
      (value "LM358PW")
      (footprint "eagle-import:SOP65P640X120-8N")
      (fields (field (name "MF") "Texas Instruments"))
      (libsource (lib "eagle-import") (part "LM358PW"))
    )
    (comp (ref "U8")
      (value "LM358PW")
      (footprint "eagle-import:SOP65P640X120-8N")
      (fields (field (name "MF") "Texas Instruments"))
      (libsource (lib "eagle-import") (part "LM358PW"))
    )
    (comp (ref "U9")
      (value "LM358PW")
      (footprint "eagle-import:SOP65P640X120-8N")
      (fields (field (name "MF") "Texas Instruments"))
      (libsource (lib "eagle-import") (part "LM358PW"))
    )
    (comp (ref "U10")
      (value "LM358PW")
      (footprint "eagle-import:SOP65P640X120-8N")
      (fields (field (name "MF") "Texas Instruments"))
      (libsource (lib "eagle-import") (part "LM358PW"))
    )
    (comp (ref "U11")
      (value "LM358PW")
      (footprint "eagle-import:SOP65P640X120-8N")
      (fields (field (name "MF") "Texas Instruments"))
      (libsource (lib "eagle-import") (part "LM358PW"))
    )
    (comp (ref "U12")
      (value "LM358PW")
      (footprint "eagle-import:SOP65P640X120-8N")
      (fields (field (name "MF") "Texas Instruments"))
      (libsource (lib "eagle-import") (part "LM358PW"))
    )
    (comp (ref "U13")
      (value "FT232HL-REEL")
      (footprint "eagle-import:QFP50P900X900X160-48N")
      (fields (field (name "MF") "FTDI, Future") (field (name "MP") "FT232HL"))
      (libsource (lib "eagle-import") (part "FT232HL-REEL"))
    )
    (comp (ref "U14")
      (value "LP2985AIM5-2.5")
      (footprint "eagle-import:SOT95P280X145-5N")
      (fields (field (name "MF") "Texas Instruments") (field (name "MP") "LP2985AIM5-2.5/NOPB"))
      (libsource (lib "eagle-import") (part "LP2985AIM5-2.5"))
    )
    (comp (ref "U15")
      (value "ICM-42605")
      (footprint "eagle-import:PQFN50P300X250X97-14N")
      (fields (field (name "MF") "TDK InvenSense"))
      (libsource (lib "eagle-import") (part "ICM-42605"))
    )
    (comp (ref "U16")
      (value "WS2812-2020")
      (footprint "eagle-import:LED_WS2812-2020")
      (fields (field (name "MF") "Worldsemi"))
      (libsource (lib "eagle-import") (part "WS2812-2020"))
    )
    (comp (ref "U22")
      (value "LM2735XMF")
      (footprint "eagle-import:SOT95P280X145-5N")
      (fields (field (name "MF") "Texas Instruments") (field (name "MP") "LM2735XMF/NOPB"))
      (libsource (lib "eagle-import") (part "LM2735XMF"))
    )
    (comp (ref "Y2")
      (value "CSTCE8M00G52A-R0")
      (footprint "eagle-import:OSC_CSTCE8M00G52A-R0")
      (fields (field (name "MF") "Murata Electronics") (field (name "MP") "CSTCE8M00G52A-R0."))
      (libsource (lib "eagle-import") (part "CSTCE8M00G52A-R0"))
    )
  )
  (nets
    (net (code "1") (name "/1V2A") (class "Default")
      (node (ref "C4") (pin "1") (pinfunction "1_1") (pintype "passive"))
      (node (ref "IC6") (pin "4") (pinfunction "VOUT_4") (pintype "bidirectional"))
      (node (ref "L1") (pin "1") (pinfunction "1_1") (pintype "passive"))
      (node (ref "R13") (pin "2") (pinfunction "2_2") (pintype "passive"))
    )
    (net (code "2") (name "/1V2LX") (class "Default")
      (node (ref "IC6") (pin "5") (pinfunction "LX_5") (pintype "bidirectional"))
      (node (ref "L1") (pin "2") (pinfunction "2_2") (pintype "passive"))
    )
    (net (code "3") (name "/1V2VIN") (class "Default")
      (node (ref "C2") (pin "1") (pinfunction "1_1") (pintype "passive"))
      (node (ref "IC6") (pin "1") (pinfunction "VIN_1") (pintype "bidirectional"))
      (node (ref "IC6") (pin "3") (pinfunction "EN_3") (pintype "bidirectional"))
      (node (ref "R5") (pin "2") (pinfunction "2_2") (pintype "passive"))
    )
    (net (code "4") (name "/BOOSTFB") (class "Default")
      (node (ref "R2") (pin "2") (pinfunction "2_2") (pintype "passive"))
      (node (ref "R3") (pin "1") (pinfunction "1_1") (pintype "passive"))
      (node (ref "U22") (pin "3") (pinfunction "FB_3") (pintype "input"))
    )
    (net (code "5") (name "/BOOSTIN") (class "Default")
      (node (ref "C5") (pin "1") (pinfunction "1_1") (pintype "passive"))
      (node (ref "L2") (pin "1") (pinfunction "1_1") (pintype "passive"))
      (node (ref "R6") (pin "2") (pinfunction "2_2") (pintype "passive"))
      (node (ref "U22") (pin "4") (pinfunction "EN_4") (pintype "input"))
      (node (ref "U22") (pin "5") (pinfunction "VIN_5") (pintype "input"))
    )
    (net (code "6") (name "/BOOSTSW") (class "Default")
      (node (ref "D1") (pin "A") (pinfunction "A_A") (pintype "passive"))
      (node (ref "L2") (pin "2") (pinfunction "2_2") (pintype "passive"))
      (node (ref "U22") (pin "1") (pinfunction "SW_1") (pintype "power_in"))
    )
    (net (code "7") (name "1V2") (class "Default")
      (node (ref "C15") (pin "1") (pinfunction "1_1") (pintype "passive"))
      (node (ref "C21") (pin "1") (pinfunction "1_1") (pintype "passive"))
      (node (ref "C7") (pin "1") (pinfunction "1_1") (pintype "passive"))
      (node (ref "IC1") (pin "G6") (pinfunction "VCC_1_G6") (pintype "bidirectional"))
      (node (ref "IC1") (pin "G7") (pinfunction "VCC_2_G7") (pintype "bidirectional"))
      (node (ref "IC1") (pin "G9") (pinfunction "VCC_3_G9") (pintype "bidirectional"))
      (node (ref "IC1") (pin "L10") (pinfunction "VCC_6_L10") (pintype "bidirectional"))
      (node (ref "IC1") (pin "L8") (pinfunction "VCC_4_L8") (pintype "bidirectional"))
      (node (ref "IC1") (pin "L9") (pinfunction "VCC_5_L9") (pintype "bidirectional"))
      (node (ref "R13") (pin "1") (pinfunction "1_1") (pintype "passive"))
    )
    (net (code "8") (name "3V3") (class "Default")
      (node (ref "C10") (pin "1") (pinfunction "1_1") (pintype "passive"))
      (node (ref "C24") (pin "1") (pinfunction "1_1") (pintype "passive"))
      (node (ref "C9") (pin "1") (pinfunction "1_1") (pintype "passive"))
      (node (ref "IC1") (pin "F10") (pinfunction "VCCIO1_1_F10") (pintype "bidirectional"))
      (node (ref "IC1") (pin "F11") (pinfunction "VCCIO1_2_F11") (pintype "bidirectional"))
      (node (ref "IC1") (pin "F6") (pinfunction "VCCIO0_1_F6") (pintype "bidirectional"))
      (node (ref "IC1") (pin "F7") (pinfunction "VCCIO0_2_F7") (pintype "bidirectional"))
      (node (ref "IC1") (pin "H11") (pinfunction "VCCIO2_1_H11") (pintype "bidirectional"))
      (node (ref "IC1") (pin "H6") (pinfunction "VCCIO7_1_H6") (pintype "bidirectional"))
      (node (ref "IC1") (pin "H7") (pinfunction "VCCIO7_2_H7") (pintype "bidirectional"))
      (node (ref "IC1") (pin "J11") (pinfunction "VCCIO2_2_J11") (pintype "bidirectional"))
      (node (ref "IC1") (pin "J6") (pinfunction "VCCIO6_1_J6") (pintype "bidirectional"))
      (node (ref "IC1") (pin "J7") (pinfunction "VCCIO6_2_J7") (pintype "bidirectional"))
      (node (ref "IC1") (pin "L6") (pinfunction "VCCIO8_L6") (pintype "bidirectional"))
      (node (ref "IC1") (pin "P10") (pinfunction "CFG_1_P10") (pintype "bidirectional"))
      (node (ref "Q1") (pin "P$1") (pinfunction "OE_P$1") (pintype "input"))
      (node (ref "Q1") (pin "P$4") (pinfunction "VCC_P$4") (pintype "power_in"))
      (node (ref "R1") (pin "2") (pinfunction "2_2") (pintype "passive"))
      (node (ref "R16") (pin "2") (pinfunction "2_2") (pintype "passive"))
      (node (ref "U4") (pin "8") (pinfunction "VCC_8") (pintype "power_in"))
      (node (ref "U6") (pin "5") (pinfunction "VOUT_5") (pintype "output"))
    )
    (net (code "9") (name "BATON") (class "Default")
      (node (ref "IC10") (pin "9") (pinfunction "BATON_9") (pintype "bidirectional"))
      (node (ref "IC11") (pin "2") (pinfunction "IO1_2") (pintype "bidirectional"))
      (node (ref "R31") (pin "1") (pinfunction "1_1") (pintype "passive"))
    )
    (net (code "10") (name "F1") (class "Default")
      (node (ref "RN16") (pin "5") (pinfunction "2_5") (pintype "passive"))
      (node (ref "RN7") (pin "8") (pinfunction "2_8") (pintype "passive"))
      (node (ref "U1") (pin "3") (pinfunction "1IN+_3") (pintype "input"))
    )
    (net (code "11") (name "F2") (class "Default")
      (node (ref "RN16") (pin "6") (pinfunction "2_6") (pintype "passive"))
      (node (ref "RN7") (pin "7") (pinfunction "2_7") (pintype "passive"))
      (node (ref "U9") (pin "3") (pinfunction "1IN+_3") (pintype "input"))
    )
    (net (code "12") (name "F3") (class "Default")
      (node (ref "RN16") (pin "7") (pinfunction "2_7") (pintype "passive"))
      (node (ref "RN7") (pin "6") (pinfunction "2_6") (pintype "passive"))
      (node (ref "U1") (pin "5") (pinfunction "2IN+_5") (pintype "input"))
    )
    (net (code "13") (name "F4") (class "Default")
      (node (ref "RN16") (pin "8") (pinfunction "2_8") (pintype "passive"))
      (node (ref "RN7") (pin "5") (pinfunction "2_5") (pintype "passive"))
      (node (ref "U9") (pin "5") (pinfunction "2IN+_5") (pintype "input"))
    )
    (net (code "14") (name "F5") (class "Default")
      (node (ref "RN15") (pin "5") (pinfunction "2_5") (pintype "passive"))
      (node (ref "RN6") (pin "8") (pinfunction "2_8") (pintype "passive"))
      (node (ref "U7") (pin "3") (pinfunction "1IN+_3") (pintype "input"))
    )
    (net (code "15") (name "F6") (class "Default")
      (node (ref "RN15") (pin "6") (pinfunction "2_6") (pintype "passive"))
      (node (ref "RN6") (pin "7") (pinfunction "2_7") (pintype "passive"))
      (node (ref "U3") (pin "3") (pinfunction "1IN+_3") (pintype "input"))
    )
    (net (code "16") (name "F7") (class "Default")
      (node (ref "RN15") (pin "7") (pinfunction "2_7") (pintype "passive"))
      (node (ref "RN6") (pin "6") (pinfunction "2_6") (pintype "passive"))
      (node (ref "U7") (pin "5") (pinfunction "2IN+_5") (pintype "input"))
    )
    (net (code "17") (name "F8") (class "Default")
      (node (ref "RN15") (pin "8") (pinfunction "2_8") (pintype "passive"))
      (node (ref "RN6") (pin "5") (pinfunction "2_5") (pintype "passive"))
      (node (ref "U3") (pin "5") (pinfunction "2IN+_5") (pintype "input"))
    )
    (net (code "18") (name "F9") (class "Default")
      (node (ref "RN14") (pin "5") (pinfunction "2_5") (pintype "passive"))
      (node (ref "RN5") (pin "8") (pinfunction "2_8") (pintype "passive"))
      (node (ref "U10") (pin "3") (pinfunction "1IN+_3") (pintype "input"))
    )
    (net (code "19") (name "F10") (class "Default")
      (node (ref "RN14") (pin "6") (pinfunction "2_6") (pintype "passive"))
      (node (ref "RN5") (pin "7") (pinfunction "2_7") (pintype "passive"))
      (node (ref "U8") (pin "3") (pinfunction "1IN+_3") (pintype "input"))
    )
    (net (code "20") (name "F11") (class "Default")
      (node (ref "RN14") (pin "7") (pinfunction "2_7") (pintype "passive"))
      (node (ref "RN5") (pin "6") (pinfunction "2_6") (pintype "passive"))
      (node (ref "U10") (pin "5") (pinfunction "2IN+_5") (pintype "input"))
    )
    (net (code "21") (name "F12") (class "Default")
      (node (ref "RN14") (pin "8") (pinfunction "2_8") (pintype "passive"))
      (node (ref "RN5") (pin "5") (pinfunction "2_5") (pintype "passive"))
      (node (ref "U8") (pin "5") (pinfunction "2IN+_5") (pintype "input"))
    )
    (net (code "22") (name "F13") (class "Default")
      (node (ref "RN13") (pin "5") (pinfunction "2_5") (pintype "passive"))
      (node (ref "RN4") (pin "8") (pinfunction "2_8") (pintype "passive"))
      (node (ref "U12") (pin "3") (pinfunction "1IN+_3") (pintype "input"))
    )
    (net (code "23") (name "F14") (class "Default")
      (node (ref "RN13") (pin "6") (pinfunction "2_6") (pintype "passive"))
      (node (ref "RN4") (pin "7") (pinfunction "2_7") (pintype "passive"))
      (node (ref "U11") (pin "3") (pinfunction "1IN+_3") (pintype "input"))
    )
    (net (code "24") (name "F15") (class "Default")
      (node (ref "RN13") (pin "7") (pinfunction "2_7") (pintype "passive"))
      (node (ref "RN4") (pin "6") (pinfunction "2_6") (pintype "passive"))
      (node (ref "U12") (pin "5") (pinfunction "2IN+_5") (pintype "input"))
    )
    (net (code "25") (name "F16") (class "Default")
      (node (ref "RN13") (pin "8") (pinfunction "2_8") (pintype "passive"))
      (node (ref "RN4") (pin "5") (pinfunction "2_5") (pintype "passive"))
      (node (ref "U11") (pin "5") (pinfunction "2IN+_5") (pintype "input"))
    )
    (net (code "26") (name "FT3V3") (class "Default")
      (node (ref "C31") (pin "1") (pinfunction "1_1") (pintype "passive"))
      (node (ref "C34") (pin "1") (pinfunction "1_1") (pintype "passive"))
      (node (ref "R22") (pin "2") (pinfunction "2_2") (pintype "passive"))
      (node (ref "R23") (pin "2") (pinfunction "2_2") (pintype "passive"))
      (node (ref "R24") (pin "2") (pinfunction "2_2") (pintype "passive"))
      (node (ref "U13") (pin "12") (pinfunction "VCCIO_12") (pintype "power_in"))
      (node (ref "U13") (pin "24") (pinfunction "VCCIO_24") (pintype "power_in"))
      (node (ref "U13") (pin "3") (pinfunction "VPHY_3") (pintype "power_in"))
      (node (ref "U13") (pin "34") (pinfunction "RESET#_34") (pintype "input"))
      (node (ref "U13") (pin "39") (pinfunction "VCCD_39") (pintype "power_in"))
      (node (ref "U13") (pin "46") (pinfunction "VCCIO_46") (pintype "power_in"))
      (node (ref "U13") (pin "8") (pinfunction "VPLL_8") (pintype "power_in"))
    )
    (net (code "27") (name "FTVCCA") (class "Default")
      (node (ref "C32") (pin "1") (pinfunction "1_1") (pintype "passive"))
      (node (ref "U13") (pin "37") (pinfunction "VCCA_37") (pintype "power_in"))
    )
    (net (code "28") (name "FTVCORE") (class "Default")
      (node (ref "C33") (pin "1") (pinfunction "1_1") (pintype "passive"))
      (node (ref "U13") (pin "38") (pinfunction "VCORE_38") (pintype "power_in"))
    )
    (net (code "29") (name "GND") (class "Default")
      (node (ref "C10") (pin "2") (pinfunction "2_2") (pintype "passive"))
      (node (ref "C11") (pin "2") (pinfunction "2_2") (pintype "passive"))
      (node (ref "C12") (pin "2") (pinfunction "2_2") (pintype "passive"))
      (node (ref "C13") (pin "2") (pinfunction "2_2") (pintype "passive"))
      (node (ref "C14") (pin "2") (pinfunction "2_2") (pintype "passive"))
      (node (ref "C15") (pin "2") (pinfunction "2_2") (pintype "passive"))
      (node (ref "C16") (pin "2") (pinfunction "2_2") (pintype "passive"))
      (node (ref "C17") (pin "2") (pinfunction "2_2") (pintype "passive"))
      (node (ref "C18") (pin "2") (pinfunction "2_2") (pintype "passive"))
      (node (ref "C19") (pin "2") (pinfunction "2_2") (pintype "passive"))
      (node (ref "C2") (pin "2") (pinfunction "2_2") (pintype "passive"))
      (node (ref "C20") (pin "2") (pinfunction "2_2") (pintype "passive"))
      (node (ref "C21") (pin "2") (pinfunction "2_2") (pintype "passive"))
      (node (ref "C22") (pin "2") (pinfunction "2_2") (pintype "passive"))
      (node (ref "C23") (pin "2") (pinfunction "2_2") (pintype "passive"))
      (node (ref "C24") (pin "2") (pinfunction "2_2") (pintype "passive"))
      (node (ref "C25") (pin "2") (pinfunction "2_2") (pintype "passive"))
      (node (ref "C26") (pin "2") (pinfunction "2_2") (pintype "passive"))
      (node (ref "C28") (pin "2") (pinfunction "2_2") (pintype "passive"))
      (node (ref "C3") (pin "2") (pinfunction "2_2") (pintype "passive"))
      (node (ref "C30") (pin "2") (pinfunction "2_2") (pintype "passive"))
      (node (ref "C31") (pin "2") (pinfunction "2_2") (pintype "passive"))
      (node (ref "C32") (pin "2") (pinfunction "2_2") (pintype "passive"))
      (node (ref "C33") (pin "2") (pinfunction "2_2") (pintype "passive"))
      (node (ref "C34") (pin "2") (pinfunction "2_2") (pintype "passive"))
      (node (ref "C35") (pin "2") (pinfunction "2_2") (pintype "passive"))
      (node (ref "C4") (pin "2") (pinfunction "2_2") (pintype "passive"))
      (node (ref "C5") (pin "2") (pinfunction "2_2") (pintype "passive"))
      (node (ref "C6") (pin "2") (pinfunction "2_2") (pintype "passive"))
      (node (ref "C7") (pin "2") (pinfunction "2_2") (pintype "passive"))
      (node (ref "C8") (pin "2") (pinfunction "2_2") (pintype "passive"))
      (node (ref "C9") (pin "2") (pinfunction "2_2") (pintype "passive"))
      (node (ref "IC1") (pin "A1") (pinfunction "GND_1_A1") (pintype "bidirectional"))
      (node (ref "IC1") (pin "A16") (pinfunction "GND_2_A16") (pintype "bidirectional"))
      (node (ref "IC1") (pin "D15") (pinfunction "GND_4_D15") (pintype "bidirectional"))
      (node (ref "IC1") (pin "D2") (pinfunction "GND_3_D2") (pintype "bidirectional"))
      (node (ref "IC1") (pin "F8") (pinfunction "GND_5_F8") (pintype "bidirectional"))
      (node (ref "IC1") (pin "F9") (pinfunction "GND_6_F9") (pintype "bidirectional"))
      (node (ref "IC1") (pin "G10") (pinfunction "GND_8_G10") (pintype "bidirectional"))
      (node (ref "IC1") (pin "G8") (pinfunction "GND_7_G8") (pintype "bidirectional"))
      (node (ref "IC1") (pin "H1") (pinfunction "GND_9_H1") (pintype "bidirectional"))
      (node (ref "IC1") (pin "H10") (pinfunction "GND_12_H10") (pintype "bidirectional"))
      (node (ref "IC1") (pin "H16") (pinfunction "GND_13_H16") (pintype "bidirectional"))
      (node (ref "IC1") (pin "H8") (pinfunction "GND_10_H8") (pintype "bidirectional"))
      (node (ref "IC1") (pin "H9") (pinfunction "GND_11_H9") (pintype "bidirectional"))
      (node (ref "IC1") (pin "J10") (pinfunction "GND_16_J10") (pintype "bidirectional"))
      (node (ref "IC1") (pin "J8") (pinfunction "GND_14_J8") (pintype "bidirectional"))
      (node (ref "IC1") (pin "J9") (pinfunction "GND_15_J9") (pintype "bidirectional"))
      (node (ref "IC1") (pin "K10") (pinfunction "GND_21_K10") (pintype "bidirectional"))
      (node (ref "IC1") (pin "K6") (pinfunction "GND_17_K6") (pintype "bidirectional"))
      (node (ref "IC1") (pin "K7") (pinfunction "GND_18_K7") (pintype "bidirectional"))
      (node (ref "IC1") (pin "K8") (pinfunction "GND_19_K8") (pintype "bidirectional"))
      (node (ref "IC1") (pin "K9") (pinfunction "GND_20_K9") (pintype "bidirectional"))
      (node (ref "IC1") (pin "N10") (pinfunction "CFG_0_N10") (pintype "bidirectional"))
      (node (ref "IC1") (pin "N15") (pinfunction "GND_23_N15") (pintype "bidirectional"))
      (node (ref "IC1") (pin "N2") (pinfunction "GND_22_N2") (pintype "bidirectional"))
      (node (ref "IC1") (pin "R10") (pinfunction "CFG_2_R10") (pintype "bidirectional"))
      (node (ref "IC1") (pin "T1") (pinfunction "GND_24_T1") (pintype "bidirectional"))
      (node (ref "IC1") (pin "T12") (pinfunction "GND_26_T12") (pintype "bidirectional"))
      (node (ref "IC1") (pin "T16") (pinfunction "GND_27_T16") (pintype "bidirectional"))
      (node (ref "IC1") (pin "T5") (pinfunction "GND_25_T5") (pintype "bidirectional"))
      (node (ref "IC10") (pin "11") (pinfunction "EP_11") (pintype "bidirectional"))
      (node (ref "IC10") (pin "6") (pinfunction "GND_6") (pintype "bidirectional"))
      (node (ref "IC11") (pin "4") (pinfunction "VSS_4") (pintype "bidirectional"))
      (node (ref "IC12") (pin "3") (pinfunction "GND_3") (pintype "power_in"))
      (node (ref "IC12") (pin "7") (pinfunction "A0_7") (pintype "input"))
      (node (ref "IC12") (pin "8") (pinfunction "A1_8") (pintype "input"))
      (node (ref "IC2") (pin "5") (pinfunction "REF1_5") (pintype "input"))
      (node (ref "IC3") (pin "5") (pinfunction "REF1_5") (pintype "input"))
      (node (ref "IC4") (pin "5") (pinfunction "REF1_5") (pintype "input"))
      (node (ref "IC5") (pin "5") (pinfunction "REF1_5") (pintype "input"))
      (node (ref "IC6") (pin "2") (pinfunction "GND_2") (pintype "bidirectional"))
      (node (ref "J2") (pin "A1/B12") (pinfunction "GND_A1/B12") (pintype "power_in"))
      (node (ref "J2") (pin "B1/A12") (pinfunction "GND_B1/A12") (pintype "power_in"))
      (node (ref "J2") (pin "S1") (pinfunction "GND_S1") (pintype "power_in"))
      (node (ref "J2") (pin "S2") (pinfunction "GND_S2") (pintype "power_in"))
      (node (ref "J2") (pin "S3") (pinfunction "GND_S3") (pintype "power_in"))
      (node (ref "J2") (pin "S4") (pinfunction "GND_S4") (pintype "power_in"))
      (node (ref "JP1") (pin "3") (pinfunction "3_3") (pintype "passive"))
      (node (ref "Q1") (pin "P$2") (pinfunction "GND_P$2") (pintype "power_in"))
      (node (ref "Q2") (pin "4") (pinfunction "S_4") (pintype "bidirectional"))
      (node (ref "R12") (pin "1") (pinfunction "1_1") (pintype "passive"))
      (node (ref "R19") (pin "1") (pinfunction "1_1") (pintype "passive"))
      (node (ref "R2") (pin "1") (pinfunction "1_1") (pintype "passive"))
      (node (ref "R20") (pin "1") (pinfunction "1_1") (pintype "passive"))
      (node (ref "R21") (pin "1") (pinfunction "1_1") (pintype "passive"))
      (node (ref "R26") (pin "2") (pinfunction "2_2") (pintype "passive"))
      (node (ref "R27") (pin "1") (pinfunction "1_1") (pintype "passive"))
      (node (ref "R28") (pin "1") (pinfunction "1_1") (pintype "passive"))
      (node (ref "R29") (pin "1") (pinfunction "1_1") (pintype "passive"))
      (node (ref "R8") (pin "1") (pinfunction "1_1") (pintype "passive"))
      (node (ref "RN11") (pin "5") (pinfunction "2_5") (pintype "passive"))
      (node (ref "RN11") (pin "6") (pinfunction "2_6") (pintype "passive"))
      (node (ref "RN11") (pin "7") (pinfunction "2_7") (pintype "passive"))
      (node (ref "RN11") (pin "8") (pinfunction "2_8") (pintype "passive"))
      (node (ref "RN12") (pin "5") (pinfunction "2_5") (pintype "passive"))
      (node (ref "RN12") (pin "6") (pinfunction "2_6") (pintype "passive"))
      (node (ref "RN12") (pin "7") (pinfunction "2_7") (pintype "passive"))
      (node (ref "RN12") (pin "8") (pinfunction "2_8") (pintype "passive"))
      (node (ref "RN13") (pin "1") (pinfunction "1_1") (pintype "passive"))
      (node (ref "RN13") (pin "2") (pinfunction "1_2") (pintype "passive"))
      (node (ref "RN13") (pin "3") (pinfunction "1_3") (pintype "passive"))
      (node (ref "RN13") (pin "4") (pinfunction "1_4") (pintype "passive"))
      (node (ref "RN14") (pin "1") (pinfunction "1_1") (pintype "passive"))
      (node (ref "RN14") (pin "2") (pinfunction "1_2") (pintype "passive"))
      (node (ref "RN14") (pin "3") (pinfunction "1_3") (pintype "passive"))
      (node (ref "RN14") (pin "4") (pinfunction "1_4") (pintype "passive"))
      (node (ref "RN15") (pin "1") (pinfunction "1_1") (pintype "passive"))
      (node (ref "RN15") (pin "2") (pinfunction "1_2") (pintype "passive"))
      (node (ref "RN15") (pin "3") (pinfunction "1_3") (pintype "passive"))
      (node (ref "RN15") (pin "4") (pinfunction "1_4") (pintype "passive"))
      (node (ref "RN16") (pin "1") (pinfunction "1_1") (pintype "passive"))
      (node (ref "RN16") (pin "2") (pinfunction "1_2") (pintype "passive"))
      (node (ref "RN16") (pin "3") (pinfunction "1_3") (pintype "passive"))
      (node (ref "RN16") (pin "4") (pinfunction "1_4") (pintype "passive"))
      (node (ref "RN21") (pin "5") (pinfunction "2_5") (pintype "passive"))
      (node (ref "RN21") (pin "6") (pinfunction "2_6") (pintype "passive"))
      (node (ref "RN21") (pin "7") (pinfunction "2_7") (pintype "passive"))
      (node (ref "RN21") (pin "8") (pinfunction "2_8") (pintype "passive"))
      (node (ref "RN22") (pin "5") (pinfunction "2_5") (pintype "passive"))
      (node (ref "RN22") (pin "6") (pinfunction "2_6") (pintype "passive"))
      (node (ref "RN22") (pin "7") (pinfunction "2_7") (pintype "passive"))
      (node (ref "RN22") (pin "8") (pinfunction "2_8") (pintype "passive"))
      (node (ref "RN23") (pin "5") (pinfunction "2_5") (pintype "passive"))
      (node (ref "RN23") (pin "6") (pinfunction "2_6") (pintype "passive"))
      (node (ref "RN23") (pin "7") (pinfunction "2_7") (pintype "passive"))
      (node (ref "RN23") (pin "8") (pinfunction "2_8") (pintype "passive"))
      (node (ref "RN24") (pin "5") (pinfunction "2_5") (pintype "passive"))
      (node (ref "RN24") (pin "6") (pinfunction "2_6") (pintype "passive"))
      (node (ref "RN24") (pin "7") (pinfunction "2_7") (pintype "passive"))
      (node (ref "RN24") (pin "8") (pinfunction "2_8") (pintype "passive"))
      (node (ref "RN8") (pin "5") (pinfunction "2_5") (pintype "passive"))
      (node (ref "RN8") (pin "6") (pinfunction "2_6") (pintype "passive"))
      (node (ref "RN8") (pin "7") (pinfunction "2_7") (pintype "passive"))
      (node (ref "RN8") (pin "8") (pinfunction "2_8") (pintype "passive"))
      (node (ref "RN9") (pin "5") (pinfunction "2_5") (pintype "passive"))
      (node (ref "RN9") (pin "6") (pinfunction "2_6") (pintype "passive"))
      (node (ref "RN9") (pin "7") (pinfunction "2_7") (pintype "passive"))
      (node (ref "RN9") (pin "8") (pinfunction "2_8") (pintype "passive"))
      (node (ref "TP2") (pin "TP") (pinfunction "TP_TP") (pintype "input"))
      (node (ref "U$1") (pin "P$1") (pinfunction "P$1_P$1") (pintype "bidirectional"))
      (node (ref "U$35") (pin "P$1") (pinfunction "P$1_P$1") (pintype "bidirectional"))
      (node (ref "U$36") (pin "P$1") (pinfunction "P$1_P$1") (pintype "bidirectional"))
      (node (ref "U$9") (pin "GND") (pinfunction "GND_GND") (pintype "bidirectional"))
      (node (ref "U1") (pin "4") (pinfunction "GND_4") (pintype "power_in"))
      (node (ref "U10") (pin "4") (pinfunction "GND_4") (pintype "power_in"))
      (node (ref "U11") (pin "4") (pinfunction "GND_4") (pintype "power_in"))
      (node (ref "U12") (pin "4") (pinfunction "GND_4") (pintype "power_in"))
      (node (ref "U13") (pin "10") (pinfunction "GND_10") (pintype "power_in"))
      (node (ref "U13") (pin "11") (pinfunction "GND_11") (pintype "power_in"))
      (node (ref "U13") (pin "22") (pinfunction "GND_22") (pintype "power_in"))
      (node (ref "U13") (pin "23") (pinfunction "GND_23") (pintype "power_in"))
      (node (ref "U13") (pin "35") (pinfunction "GND_35") (pintype "power_in"))
      (node (ref "U13") (pin "36") (pinfunction "GND_36") (pintype "power_in"))
      (node (ref "U13") (pin "4") (pinfunction "AGND_4") (pintype "power_in"))
      (node (ref "U13") (pin "41") (pinfunction "AGND_41") (pintype "power_in"))
      (node (ref "U13") (pin "42") (pinfunction "TEST_42") (pintype "input"))
      (node (ref "U13") (pin "47") (pinfunction "GND_47") (pintype "power_in"))
      (node (ref "U13") (pin "48") (pinfunction "GND_48") (pintype "power_in"))
      (node (ref "U13") (pin "9") (pinfunction "AGND_9") (pintype "power_in"))
      (node (ref "U14") (pin "2") (pinfunction "GND_2") (pintype "power_in"))
      (node (ref "U15") (pin "1") (pinfunction "AP_SDO/AP_ADO_1") (pintype "output"))
      (node (ref "U15") (pin "10") (pinfunction "RESV_4_10") (pintype "bidirectional"))
      (node (ref "U15") (pin "11") (pinfunction "RESV_5_11") (pintype "bidirectional"))
      (node (ref "U15") (pin "2") (pinfunction "RESV_1_2") (pintype "bidirectional"))
      (node (ref "U15") (pin "3") (pinfunction "RESV_2_3") (pintype "bidirectional"))
      (node (ref "U15") (pin "6") (pinfunction "GND_6") (pintype "power_in"))
      (node (ref "U15") (pin "7") (pinfunction "RESV_3_7") (pintype "bidirectional"))
      (node (ref "U15") (pin "9") (pinfunction "INT2/FSYNC_9") (pintype "bidirectional"))
      (node (ref "U16") (pin "2") (pinfunction "GND_2") (pintype "power_in"))
      (node (ref "U22") (pin "2") (pinfunction "GND_2") (pintype "power_in"))
      (node (ref "U3") (pin "4") (pinfunction "GND_4") (pintype "power_in"))
      (node (ref "U4") (pin "4") (pinfunction "GND_4") (pintype "power_in"))
      (node (ref "U5") (pin "2") (pinfunction "GND_2") (pintype "power_in"))
      (node (ref "U6") (pin "2") (pinfunction "GND_2") (pintype "power_in"))
      (node (ref "U7") (pin "4") (pinfunction "GND_4") (pintype "power_in"))
      (node (ref "U8") (pin "4") (pinfunction "GND_4") (pintype "power_in"))
      (node (ref "U9") (pin "4") (pinfunction "GND_4") (pintype "power_in"))
      (node (ref "Y2") (pin "2") (pinfunction "GND_2") (pintype "power_in"))
    )
    (net (code "30") (name "IO1") (class "Default")
      (node (ref "IC1") (pin "R1") (pinfunction "PL35B_R1") (pintype "bidirectional"))
      (node (ref "U$9") (pin "MISO") (pinfunction "MISO_MISO") (pintype "bidirectional"))
    )
    (net (code "31") (name "IO2") (class "Default")
      (node (ref "IC1") (pin "R2") (pinfunction "PL38C_R2") (pintype "bidirectional"))
      (node (ref "U$9") (pin "MOSI") (pinfunction "MOSI_MOSI") (pintype "bidirectional"))
    )
    (net (code "32") (name "IO3") (class "Default")
      (node (ref "IC1") (pin "T2") (pinfunction "PL38D_T2") (pintype "bidirectional"))
      (node (ref "U$9") (pin "SCK") (pinfunction "SCK_SCK") (pintype "bidirectional"))
    )
    (net (code "33") (name "IO4") (class "Default")
      (node (ref "IC1") (pin "R3") (pinfunction "PL41B_R3") (pintype "bidirectional"))
      (node (ref "JP1") (pin "1") (pinfunction "1_1") (pintype "passive"))
      (node (ref "JP5") (pin "1") (pinfunction "1_1") (pintype "passive"))
    )
    (net (code "34") (name "IO5") (class "Default")
      (node (ref "IC1") (pin "T3") (pinfunction "PL41D_T3") (pintype "bidirectional"))
      (node (ref "U$9") (pin "CSN") (pinfunction "CSN_CSN") (pintype "bidirectional"))
    )
    (net (code "35") (name "IO6") (class "Default")
      (node (ref "IC1") (pin "R4") (pinfunction "PL41C_R4") (pintype "bidirectional"))
      (node (ref "JP1") (pin "2") (pinfunction "2_2") (pintype "passive"))
      (node (ref "JP4") (pin "1") (pinfunction "1_1") (pintype "passive"))
    )
    (net (code "36") (name "IO7") (class "Default")
      (node (ref "IC1") (pin "T4") (pinfunction "PL44B_T4") (pintype "bidirectional"))
      (node (ref "U$9") (pin "CE") (pinfunction "CE_CE") (pintype "bidirectional"))
    )
    (net (code "37") (name "IO9") (class "Default")
      (node (ref "IC1") (pin "P6") (pinfunction "PL47C_P6") (pintype "bidirectional"))
      (node (ref "R14") (pin "2") (pinfunction "2_2") (pintype "passive"))
    )
    (net (code "38") (name "JTAG_TCK") (class "Default")
      (node (ref "IC1") (pin "T10") (pinfunction "TCK_T10") (pintype "bidirectional"))
      (node (ref "R8") (pin "2") (pinfunction "2_2") (pintype "passive"))
      (node (ref "U13") (pin "13") (pinfunction "ADBUS0_13") (pintype "bidirectional"))
    )
    (net (code "39") (name "JTAG_TDI") (class "Default")
      (node (ref "IC1") (pin "R11") (pinfunction "TDI_R11") (pintype "bidirectional"))
      (node (ref "U13") (pin "14") (pinfunction "ADBUS1_14") (pintype "bidirectional"))
    )
    (net (code "40") (name "JTAG_TDO") (class "Default")
      (node (ref "IC1") (pin "M10") (pinfunction "TDO_M10") (pintype "bidirectional"))
      (node (ref "U13") (pin "15") (pinfunction "ADBUS2_15") (pintype "bidirectional"))
    )
    (net (code "41") (name "JTAG_TMS") (class "Default")
      (node (ref "IC1") (pin "T11") (pinfunction "TMS_T11") (pintype "bidirectional"))
      (node (ref "U13") (pin "16") (pinfunction "ADBUS3_16") (pintype "bidirectional"))
    )
    (net (code "42") (name "M1") (class "Default")
      (node (ref "RN17") (pin "1") (pinfunction "1_1") (pintype "passive"))
      (node (ref "RN21") (pin "4") (pinfunction "1_4") (pintype "passive"))
      (node (ref "U1") (pin "2") (pinfunction "1IN-_2") (pintype "input"))
    )
    (net (code "43") (name "M2") (class "Default")
      (node (ref "RN17") (pin "2") (pinfunction "1_2") (pintype "passive"))
      (node (ref "RN21") (pin "3") (pinfunction "1_3") (pintype "passive"))
      (node (ref "U9") (pin "2") (pinfunction "1IN-_2") (pintype "input"))
    )
    (net (code "44") (name "M3") (class "Default")
      (node (ref "RN17") (pin "3") (pinfunction "1_3") (pintype "passive"))
      (node (ref "RN21") (pin "2") (pinfunction "1_2") (pintype "passive"))
      (node (ref "U1") (pin "6") (pinfunction "2IN-_6") (pintype "input"))
    )
    (net (code "45") (name "M4") (class "Default")
      (node (ref "RN17") (pin "4") (pinfunction "1_4") (pintype "passive"))
      (node (ref "RN21") (pin "1") (pinfunction "1_1") (pintype "passive"))
      (node (ref "U9") (pin "6") (pinfunction "2IN-_6") (pintype "input"))
    )
    (net (code "46") (name "M5") (class "Default")
      (node (ref "RN18") (pin "1") (pinfunction "1_1") (pintype "passive"))
      (node (ref "RN22") (pin "4") (pinfunction "1_4") (pintype "passive"))
      (node (ref "U7") (pin "2") (pinfunction "1IN-_2") (pintype "input"))
    )
    (net (code "47") (name "M6") (class "Default")
      (node (ref "RN18") (pin "2") (pinfunction "1_2") (pintype "passive"))
      (node (ref "RN22") (pin "3") (pinfunction "1_3") (pintype "passive"))
      (node (ref "U3") (pin "2") (pinfunction "1IN-_2") (pintype "input"))
    )
    (net (code "48") (name "M7") (class "Default")
      (node (ref "RN18") (pin "3") (pinfunction "1_3") (pintype "passive"))
      (node (ref "RN22") (pin "2") (pinfunction "1_2") (pintype "passive"))
      (node (ref "U7") (pin "6") (pinfunction "2IN-_6") (pintype "input"))
    )
    (net (code "49") (name "M8") (class "Default")
      (node (ref "RN18") (pin "4") (pinfunction "1_4") (pintype "passive"))
      (node (ref "RN22") (pin "1") (pinfunction "1_1") (pintype "passive"))
      (node (ref "U3") (pin "6") (pinfunction "2IN-_6") (pintype "input"))
    )
    (net (code "50") (name "M9") (class "Default")
      (node (ref "RN19") (pin "1") (pinfunction "1_1") (pintype "passive"))
      (node (ref "RN23") (pin "4") (pinfunction "1_4") (pintype "passive"))
      (node (ref "U10") (pin "2") (pinfunction "1IN-_2") (pintype "input"))
    )
    (net (code "51") (name "M10") (class "Default")
      (node (ref "RN19") (pin "2") (pinfunction "1_2") (pintype "passive"))
      (node (ref "RN23") (pin "3") (pinfunction "1_3") (pintype "passive"))
      (node (ref "U8") (pin "2") (pinfunction "1IN-_2") (pintype "input"))
    )
    (net (code "52") (name "M11") (class "Default")
      (node (ref "RN19") (pin "3") (pinfunction "1_3") (pintype "passive"))
      (node (ref "RN23") (pin "2") (pinfunction "1_2") (pintype "passive"))
      (node (ref "U10") (pin "6") (pinfunction "2IN-_6") (pintype "input"))
    )
    (net (code "53") (name "M12") (class "Default")
      (node (ref "RN19") (pin "4") (pinfunction "1_4") (pintype "passive"))
      (node (ref "RN23") (pin "1") (pinfunction "1_1") (pintype "passive"))
      (node (ref "U8") (pin "6") (pinfunction "2IN-_6") (pintype "input"))
    )
    (net (code "54") (name "M13") (class "Default")
      (node (ref "RN20") (pin "1") (pinfunction "1_1") (pintype "passive"))
      (node (ref "RN24") (pin "4") (pinfunction "1_4") (pintype "passive"))
      (node (ref "U12") (pin "2") (pinfunction "1IN-_2") (pintype "input"))
    )
    (net (code "55") (name "M14") (class "Default")
      (node (ref "RN20") (pin "2") (pinfunction "1_2") (pintype "passive"))
      (node (ref "RN24") (pin "3") (pinfunction "1_3") (pintype "passive"))
      (node (ref "U11") (pin "2") (pinfunction "1IN-_2") (pintype "input"))
    )
    (net (code "56") (name "M15") (class "Default")
      (node (ref "RN20") (pin "3") (pinfunction "1_3") (pintype "passive"))
      (node (ref "RN24") (pin "2") (pinfunction "1_2") (pintype "passive"))
      (node (ref "U12") (pin "6") (pinfunction "2IN-_6") (pintype "input"))
    )
    (net (code "57") (name "M16") (class "Default")
      (node (ref "RN20") (pin "4") (pinfunction "1_4") (pintype "passive"))
      (node (ref "RN24") (pin "1") (pinfunction "1_1") (pintype "passive"))
      (node (ref "U11") (pin "6") (pinfunction "2IN-_6") (pintype "input"))
    )
    (net (code "58") (name "MCLK") (class "Default")
      (node (ref "IC1") (pin "M2") (pinfunction "PL26D_M2") (pintype "bidirectional"))
      (node (ref "Q1") (pin "P$3") (pinfunction "FO_P$3") (pintype "output"))
    )
    (net (code "59") (name "NCHG") (class "Default")
      (node (ref "IC10") (pin "4") (pinfunction "~{CHG}_4") (pintype "bidirectional"))
      (node (ref "IC11") (pin "3") (pinfunction "IO2_3") (pintype "bidirectional"))
    )
    (net (code "60") (name "NPPR") (class "Default")
      (node (ref "IC10") (pin "3") (pinfunction "~{PPR}_3") (pintype "bidirectional"))
      (node (ref "IC11") (pin "5") (pinfunction "IO3_5") (pintype "bidirectional"))
    )
    (net (code "61") (name "Net-(D2-A)") (class "Default")
      (node (ref "D2") (pin "1") (pinfunction "A_1") (pintype "passive"))
      (node (ref "D4") (pin "A") (pinfunction "A_A") (pintype "passive"))
      (node (ref "Q2") (pin "3") (pinfunction "G_3") (pintype "bidirectional"))
      (node (ref "R12") (pin "2") (pinfunction "2_2") (pintype "passive"))
    )
    (net (code "62") (name "Net-(IC1-INITN)") (class "Default")
      (node (ref "IC1") (pin "T9") (pinfunction "INITN_T9") (pintype "bidirectional"))
      (node (ref "R1") (pin "1") (pinfunction "1_1") (pintype "passive"))
    )
    (net (code "63") (name "Net-(IC10-IMIN)") (class "Default")
      (node (ref "IC10") (pin "7") (pinfunction "IMIN_7") (pintype "bidirectional"))
      (node (ref "R28") (pin "2") (pinfunction "2_2") (pintype "passive"))
    )
    (net (code "64") (name "Net-(IC10-IREF)") (class "Default")
      (node (ref "IC10") (pin "8") (pinfunction "IREF_8") (pintype "bidirectional"))
      (node (ref "R20") (pin "2") (pinfunction "2_2") (pintype "passive"))
    )
    (net (code "65") (name "Net-(IC10-TIME)") (class "Default")
      (node (ref "IC10") (pin "5") (pinfunction "TIME_5") (pintype "bidirectional"))
      (node (ref "R19") (pin "2") (pinfunction "2_2") (pintype "passive"))
    )
    (net (code "66") (name "Net-(J2-CC1)") (class "Default")
      (node (ref "J2") (pin "A5") (pinfunction "CC1_A5") (pintype "bidirectional"))
      (node (ref "R27") (pin "2") (pinfunction "2_2") (pintype "passive"))
    )
    (net (code "67") (name "Net-(J2-CC2)") (class "Default")
      (node (ref "J2") (pin "B5") (pinfunction "CC2_B5") (pintype "bidirectional"))
      (node (ref "R26") (pin "1") (pinfunction "1_1") (pintype "passive"))
    )
    (net (code "68") (name "Net-(J2-VBUS-PadA4{slash}B9)") (class "Default")
      (node (ref "J2") (pin "A4/B9") (pinfunction "VBUS_A4/B9") (pintype "power_in"))
      (node (ref "J2") (pin "B4/A9") (pinfunction "VBUS_B4/A9") (pintype "power_in"))
      (node (ref "R25") (pin "1") (pinfunction "1_1") (pintype "passive"))
    )
    (net (code "69") (name "Net-(JP3-Pad2)") (class "Default")
      (node (ref "JP3") (pin "2") (pinfunction "2_2") (pintype "passive"))
      (node (ref "TP1") (pin "TP") (pinfunction "TP_TP") (pintype "input"))
    )
    (net (code "70") (name "Net-(JP4-Pad2)") (class "Default")
      (node (ref "JP4") (pin "2") (pinfunction "2_2") (pintype "passive"))
      (node (ref "TP3") (pin "TP") (pinfunction "TP_TP") (pintype "input"))
    )
    (net (code "71") (name "Net-(JP5-Pad2)") (class "Default")
      (node (ref "JP5") (pin "2") (pinfunction "2_2") (pintype "passive"))
      (node (ref "TP4") (pin "TP") (pinfunction "TP_TP") (pintype "input"))
    )
    (net (code "72") (name "Net-(RN25A-2)") (class "Default")
      (node (ref "RN25") (pin "8") (pinfunction "2_8") (pintype "passive"))
      (node (ref "U$18") (pin "P$1") (pinfunction "P$1_P$1") (pintype "bidirectional"))
    )
    (net (code "73") (name "Net-(RN25B-2)") (class "Default")
      (node (ref "RN25") (pin "7") (pinfunction "2_7") (pintype "passive"))
      (node (ref "U$17") (pin "P$1") (pinfunction "P$1_P$1") (pintype "bidirectional"))
    )
    (net (code "74") (name "Net-(RN25C-2)") (class "Default")
      (node (ref "RN25") (pin "6") (pinfunction "2_6") (pintype "passive"))
      (node (ref "U$16") (pin "P$1") (pinfunction "P$1_P$1") (pintype "bidirectional"))
    )
    (net (code "75") (name "Net-(RN25D-2)") (class "Default")
      (node (ref "RN25") (pin "5") (pinfunction "2_5") (pintype "passive"))
      (node (ref "U$15") (pin "P$1") (pinfunction "P$1_P$1") (pintype "bidirectional"))
    )
    (net (code "76") (name "Net-(RN26A-2)") (class "Default")
      (node (ref "RN26") (pin "8") (pinfunction "2_8") (pintype "passive"))
      (node (ref "U$14") (pin "P$1") (pinfunction "P$1_P$1") (pintype "bidirectional"))
    )
    (net (code "77") (name "Net-(RN26B-2)") (class "Default")
      (node (ref "RN26") (pin "7") (pinfunction "2_7") (pintype "passive"))
      (node (ref "U$13") (pin "P$1") (pinfunction "P$1_P$1") (pintype "bidirectional"))
    )
    (net (code "78") (name "Net-(RN26C-2)") (class "Default")
      (node (ref "RN26") (pin "6") (pinfunction "2_6") (pintype "passive"))
      (node (ref "U$12") (pin "P$1") (pinfunction "P$1_P$1") (pintype "bidirectional"))
    )
    (net (code "79") (name "Net-(RN26D-2)") (class "Default")
      (node (ref "RN26") (pin "5") (pinfunction "2_5") (pintype "passive"))
      (node (ref "U$11") (pin "P$1") (pinfunction "P$1_P$1") (pintype "bidirectional"))
    )
    (net (code "80") (name "Net-(RN27A-2)") (class "Default")
      (node (ref "RN27") (pin "8") (pinfunction "2_8") (pintype "passive"))
      (node (ref "U$10") (pin "P$1") (pinfunction "P$1_P$1") (pintype "bidirectional"))
    )
    (net (code "81") (name "Net-(RN27B-2)") (class "Default")
      (node (ref "RN27") (pin "7") (pinfunction "2_7") (pintype "passive"))
      (node (ref "U$8") (pin "P$1") (pinfunction "P$1_P$1") (pintype "bidirectional"))
    )
    (net (code "82") (name "Net-(RN27C-2)") (class "Default")
      (node (ref "RN27") (pin "6") (pinfunction "2_6") (pintype "passive"))
      (node (ref "U$7") (pin "P$1") (pinfunction "P$1_P$1") (pintype "bidirectional"))
    )
    (net (code "83") (name "Net-(RN27D-2)") (class "Default")
      (node (ref "RN27") (pin "5") (pinfunction "2_5") (pintype "passive"))
      (node (ref "U$6") (pin "P$1") (pinfunction "P$1_P$1") (pintype "bidirectional"))
    )
    (net (code "84") (name "Net-(RN28A-2)") (class "Default")
      (node (ref "RN28") (pin "8") (pinfunction "2_8") (pintype "passive"))
      (node (ref "U$5") (pin "P$1") (pinfunction "P$1_P$1") (pintype "bidirectional"))
    )
    (net (code "85") (name "Net-(RN28B-2)") (class "Default")
      (node (ref "RN28") (pin "7") (pinfunction "2_7") (pintype "passive"))
      (node (ref "U$4") (pin "P$1") (pinfunction "P$1_P$1") (pintype "bidirectional"))
    )
    (net (code "86") (name "Net-(RN28C-2)") (class "Default")
      (node (ref "RN28") (pin "6") (pinfunction "2_6") (pintype "passive"))
      (node (ref "U$3") (pin "P$1") (pinfunction "P$1_P$1") (pintype "bidirectional"))
    )
    (net (code "87") (name "Net-(RN28D-2)") (class "Default")
      (node (ref "RN28") (pin "5") (pinfunction "2_5") (pintype "passive"))
      (node (ref "U$2") (pin "P$1") (pinfunction "P$1_P$1") (pintype "bidirectional"))
    )
    (net (code "88") (name "Net-(U5-BYPASS)") (class "Default")
      (node (ref "C20") (pin "1") (pinfunction "1_1") (pintype "passive"))
      (node (ref "U5") (pin "4") (pinfunction "BYPASS_4") (pintype "bidirectional"))
    )
    (net (code "89") (name "Net-(U5-ON{slash}OFF)") (class "Default")
      (node (ref "C6") (pin "1") (pinfunction "1_1") (pintype "passive"))
      (node (ref "R10") (pin "2") (pinfunction "2_2") (pintype "passive"))
      (node (ref "U5") (pin "1") (pinfunction "VIN_1") (pintype "input"))
      (node (ref "U5") (pin "3") (pinfunction "ON/OFF_3") (pintype "input"))
    )
    (net (code "90") (name "Net-(U6-BYPASS)") (class "Default")
      (node (ref "C12") (pin "1") (pinfunction "1_1") (pintype "passive"))
      (node (ref "U6") (pin "4") (pinfunction "BYPASS_4") (pintype "bidirectional"))
    )
    (net (code "91") (name "Net-(U6-ON{slash}OFF)") (class "Default")
      (node (ref "C14") (pin "1") (pinfunction "1_1") (pintype "passive"))
      (node (ref "R11") (pin "2") (pinfunction "2_2") (pintype "passive"))
      (node (ref "U6") (pin "1") (pinfunction "VIN_1") (pintype "input"))
      (node (ref "U6") (pin "3") (pinfunction "ON/OFF_3") (pintype "input"))
    )
    (net (code "92") (name "Net-(U13-EECLK)") (class "Default")
      (node (ref "R23") (pin "1") (pinfunction "1_1") (pintype "passive"))
      (node (ref "U13") (pin "44") (pinfunction "EECLK_44") (pintype "output"))
    )
    (net (code "93") (name "Net-(U13-EECS)") (class "Default")
      (node (ref "R22") (pin "1") (pinfunction "1_1") (pintype "passive"))
      (node (ref "U13") (pin "45") (pinfunction "EECS_45") (pintype "bidirectional"))
    )
    (net (code "94") (name "Net-(U13-EEDATA)") (class "Default")
      (node (ref "R24") (pin "1") (pinfunction "1_1") (pintype "passive"))
      (node (ref "U13") (pin "43") (pinfunction "EEDATA_43") (pintype "bidirectional"))
    )
    (net (code "95") (name "Net-(U13-REF)") (class "Default")
      (node (ref "R21") (pin "2") (pinfunction "2_2") (pintype "passive"))
      (node (ref "U13") (pin "5") (pinfunction "REF_5") (pintype "input"))
    )
    (net (code "96") (name "Net-(U14-ON{slash}OFF)") (class "Default")
      (node (ref "C25") (pin "1") (pinfunction "1_1") (pintype "passive"))
      (node (ref "R15") (pin "2") (pinfunction "2_2") (pintype "passive"))
      (node (ref "U14") (pin "1") (pinfunction "VIN_1") (pintype "input"))
      (node (ref "U14") (pin "3") (pinfunction "ON/OFF_3") (pintype "input"))
    )
    (net (code "97") (name "Net-(U16-DI)") (class "Default")
      (node (ref "R14") (pin "1") (pinfunction "1_1") (pintype "passive"))
      (node (ref "U16") (pin "3") (pinfunction "DI_3") (pintype "input"))
    )
    (net (code "98") (name "Net-(U16-VDD)") (class "Default")
      (node (ref "C11") (pin "1") (pinfunction "1_1") (pintype "passive"))
      (node (ref "R7") (pin "1") (pinfunction "1_1") (pintype "passive"))
      (node (ref "U16") (pin "4") (pinfunction "VDD_4") (pintype "power_in"))
    )
    (net (code "99") (name "O1") (class "Default")
      (node (ref "RN17") (pin "8") (pinfunction "2_8") (pintype "passive"))
      (node (ref "U$20") (pin "P$1") (pinfunction "P$1_P$1") (pintype "bidirectional"))
      (node (ref "U1") (pin "1") (pinfunction "1OUT_1") (pintype "output"))
    )
    (net (code "100") (name "O2") (class "Default")
      (node (ref "RN17") (pin "7") (pinfunction "2_7") (pintype "passive"))
      (node (ref "U$21") (pin "P$1") (pinfunction "P$1_P$1") (pintype "bidirectional"))
      (node (ref "U9") (pin "1") (pinfunction "1OUT_1") (pintype "output"))
    )
    (net (code "101") (name "O3") (class "Default")
      (node (ref "RN17") (pin "6") (pinfunction "2_6") (pintype "passive"))
      (node (ref "U$19") (pin "P$1") (pinfunction "P$1_P$1") (pintype "bidirectional"))
      (node (ref "U1") (pin "7") (pinfunction "2OUT_7") (pintype "output"))
    )
    (net (code "102") (name "O4") (class "Default")
      (node (ref "RN17") (pin "5") (pinfunction "2_5") (pintype "passive"))
      (node (ref "U$22") (pin "P$1") (pinfunction "P$1_P$1") (pintype "bidirectional"))
      (node (ref "U9") (pin "7") (pinfunction "2OUT_7") (pintype "output"))
    )
    (net (code "103") (name "O5") (class "Default")
      (node (ref "RN18") (pin "8") (pinfunction "2_8") (pintype "passive"))
      (node (ref "U$23") (pin "P$1") (pinfunction "P$1_P$1") (pintype "bidirectional"))
      (node (ref "U7") (pin "1") (pinfunction "1OUT_1") (pintype "output"))
    )
    (net (code "104") (name "O6") (class "Default")
      (node (ref "RN18") (pin "7") (pinfunction "2_7") (pintype "passive"))
      (node (ref "U$24") (pin "P$1") (pinfunction "P$1_P$1") (pintype "bidirectional"))
      (node (ref "U3") (pin "1") (pinfunction "1OUT_1") (pintype "output"))
    )
    (net (code "105") (name "O7") (class "Default")
      (node (ref "RN18") (pin "6") (pinfunction "2_6") (pintype "passive"))
      (node (ref "U$25") (pin "P$1") (pinfunction "P$1_P$1") (pintype "bidirectional"))
      (node (ref "U7") (pin "7") (pinfunction "2OUT_7") (pintype "output"))
    )
    (net (code "106") (name "O8") (class "Default")
      (node (ref "RN18") (pin "5") (pinfunction "2_5") (pintype "passive"))
      (node (ref "U$26") (pin "P$1") (pinfunction "P$1_P$1") (pintype "bidirectional"))
      (node (ref "U3") (pin "7") (pinfunction "2OUT_7") (pintype "output"))
    )
    (net (code "107") (name "O9") (class "Default")
      (node (ref "RN19") (pin "8") (pinfunction "2_8") (pintype "passive"))
      (node (ref "U$27") (pin "P$1") (pinfunction "P$1_P$1") (pintype "bidirectional"))
      (node (ref "U10") (pin "1") (pinfunction "1OUT_1") (pintype "output"))
    )
    (net (code "108") (name "O10") (class "Default")
      (node (ref "RN19") (pin "7") (pinfunction "2_7") (pintype "passive"))
      (node (ref "U$28") (pin "P$1") (pinfunction "P$1_P$1") (pintype "bidirectional"))
      (node (ref "U8") (pin "1") (pinfunction "1OUT_1") (pintype "output"))
    )
    (net (code "109") (name "O11") (class "Default")
      (node (ref "RN19") (pin "6") (pinfunction "2_6") (pintype "passive"))
      (node (ref "U$29") (pin "P$1") (pinfunction "P$1_P$1") (pintype "bidirectional"))
      (node (ref "U10") (pin "7") (pinfunction "2OUT_7") (pintype "output"))
    )
    (net (code "110") (name "O12") (class "Default")
      (node (ref "RN19") (pin "5") (pinfunction "2_5") (pintype "passive"))
      (node (ref "U$30") (pin "P$1") (pinfunction "P$1_P$1") (pintype "bidirectional"))
      (node (ref "U8") (pin "7") (pinfunction "2OUT_7") (pintype "output"))
    )
    (net (code "111") (name "O13") (class "Default")
      (node (ref "RN20") (pin "8") (pinfunction "2_8") (pintype "passive"))
      (node (ref "U$31") (pin "P$1") (pinfunction "P$1_P$1") (pintype "bidirectional"))
      (node (ref "U12") (pin "1") (pinfunction "1OUT_1") (pintype "output"))
    )
    (net (code "112") (name "O14") (class "Default")
      (node (ref "RN20") (pin "7") (pinfunction "2_7") (pintype "passive"))
      (node (ref "U$32") (pin "P$1") (pinfunction "P$1_P$1") (pintype "bidirectional"))
      (node (ref "U11") (pin "1") (pinfunction "1OUT_1") (pintype "output"))
    )
    (net (code "113") (name "O15") (class "Default")
      (node (ref "RN20") (pin "6") (pinfunction "2_6") (pintype "passive"))
      (node (ref "U$33") (pin "P$1") (pinfunction "P$1_P$1") (pintype "bidirectional"))
      (node (ref "U12") (pin "7") (pinfunction "2OUT_7") (pintype "output"))
    )
    (net (code "114") (name "O16") (class "Default")
      (node (ref "RN20") (pin "5") (pinfunction "2_5") (pintype "passive"))
      (node (ref "U$34") (pin "P$1") (pinfunction "P$1_P$1") (pintype "bidirectional"))
      (node (ref "U11") (pin "7") (pinfunction "2OUT_7") (pintype "output"))
    )
    (net (code "115") (name "OSCI") (class "Default")
      (node (ref "U13") (pin "1") (pinfunction "OSCI_1") (pintype "input"))
      (node (ref "Y2") (pin "1") (pinfunction "IN_1") (pintype "input"))
    )
    (net (code "116") (name "OSCO") (class "Default")
      (node (ref "U13") (pin "2") (pinfunction "OSCO_2") (pintype "output"))
      (node (ref "Y2") (pin "3") (pinfunction "OUT_3") (pintype "output"))
    )
    (net (code "117") (name "PCSN") (class "Default")
      (node (ref "IC1") (pin "N8") (pinfunction "PB15A_N8") (pintype "bidirectional"))
      (node (ref "U4") (pin "1") (pinfunction "CS_1") (pintype "bidirectional"))
    )
    (net (code "118") (name "PMISO") (class "Default")
      (node (ref "IC1") (pin "T7") (pinfunction "PB11A_T7") (pintype "bidirectional"))
      (node (ref "U4") (pin "2") (pinfunction "MISO_2") (pintype "bidirectional"))
    )
    (net (code "119") (name "PMOSI") (class "Default")
      (node (ref "IC1") (pin "T8") (pinfunction "PB11B_T8") (pintype "bidirectional"))
      (node (ref "U4") (pin "5") (pinfunction "MOSI_5") (pintype "bidirectional"))
    )
    (net (code "120") (name "PROGRAMN") (class "Default")
      (node (ref "IC1") (pin "R9") (pinfunction "PROGRAMN_R9") (pintype "bidirectional"))
      (node (ref "JP2") (pin "2") (pinfunction "2_2") (pintype "passive"))
      (node (ref "R16") (pin "1") (pinfunction "1_1") (pintype "passive"))
    )
    (net (code "121") (name "PSCK") (class "Default")
      (node (ref "IC1") (pin "N9") (pinfunction "CCLK_N9") (pintype "bidirectional"))
      (node (ref "U4") (pin "6") (pinfunction "SCK_6") (pintype "bidirectional"))
    )
    (net (code "122") (name "R1R") (class "Default")
      (node (ref "IC1") (pin "C5") (pinfunction "PT15A_C5") (pintype "bidirectional"))
      (node (ref "IC2") (pin "4") (pinfunction "I/O3_4") (pintype "bidirectional"))
      (node (ref "RN1") (pin "4") (pinfunction "1_4") (pintype "passive"))
      (node (ref "RN28") (pin "4") (pinfunction "1_4") (pintype "passive"))
      (node (ref "RN8") (pin "1") (pinfunction "1_1") (pintype "passive"))
    )
    (net (code "123") (name "R1T") (class "Default")
      (node (ref "IC1") (pin "B3") (pinfunction "PT4B_B3") (pintype "bidirectional"))
      (node (ref "RN1") (pin "5") (pinfunction "2_5") (pintype "passive"))
    )
    (net (code "124") (name "R2R") (class "Default")
      (node (ref "IC1") (pin "A2") (pinfunction "PT4A_A2") (pintype "bidirectional"))
      (node (ref "IC2") (pin "6") (pinfunction "I/O4_6") (pintype "bidirectional"))
      (node (ref "RN1") (pin "3") (pinfunction "1_3") (pintype "passive"))
      (node (ref "RN28") (pin "3") (pinfunction "1_3") (pintype "passive"))
      (node (ref "RN8") (pin "2") (pinfunction "1_2") (pintype "passive"))
    )
    (net (code "125") (name "R2T") (class "Default")
      (node (ref "IC1") (pin "A3") (pinfunction "PT6A_A3") (pintype "bidirectional"))
      (node (ref "RN1") (pin "6") (pinfunction "2_6") (pintype "passive"))
    )
    (net (code "126") (name "R3R") (class "Default")
      (node (ref "IC1") (pin "B5") (pinfunction "PT15B_B5") (pintype "bidirectional"))
      (node (ref "IC2") (pin "3") (pinfunction "I/O2_3") (pintype "bidirectional"))
      (node (ref "RN1") (pin "2") (pinfunction "1_2") (pintype "passive"))
      (node (ref "RN28") (pin "2") (pinfunction "1_2") (pintype "passive"))
      (node (ref "RN8") (pin "3") (pinfunction "1_3") (pintype "passive"))
    )
    (net (code "127") (name "R3T") (class "Default")
      (node (ref "IC1") (pin "B4") (pinfunction "PT11B_B4") (pintype "bidirectional"))
      (node (ref "RN1") (pin "7") (pinfunction "2_7") (pintype "passive"))
    )
    (net (code "128") (name "R4R") (class "Default")
      (node (ref "IC1") (pin "A5") (pinfunction "PT18A_A5") (pintype "bidirectional"))
      (node (ref "IC2") (pin "1") (pinfunction "I/O_1") (pintype "bidirectional"))
      (node (ref "RN1") (pin "1") (pinfunction "1_1") (pintype "passive"))
      (node (ref "RN28") (pin "1") (pinfunction "1_1") (pintype "passive"))
      (node (ref "RN8") (pin "4") (pinfunction "1_4") (pintype "passive"))
    )
    (net (code "129") (name "R4T") (class "Default")
      (node (ref "IC1") (pin "A4") (pinfunction "PT6B_A4") (pintype "bidirectional"))
      (node (ref "RN1") (pin "8") (pinfunction "2_8") (pintype "passive"))
    )
    (net (code "130") (name "R5R") (class "Default")
      (node (ref "IC1") (pin "B6") (pinfunction "PT22B_B6") (pintype "bidirectional"))
      (node (ref "IC3") (pin "3") (pinfunction "I/O2_3") (pintype "bidirectional"))
      (node (ref "RN10") (pin "4") (pinfunction "1_4") (pintype "passive"))
      (node (ref "RN27") (pin "4") (pinfunction "1_4") (pintype "passive"))
      (node (ref "RN9") (pin "1") (pinfunction "1_1") (pintype "passive"))
    )
    (net (code "131") (name "R5T") (class "Default")
      (node (ref "IC1") (pin "B7") (pinfunction "PT27B_B7") (pintype "bidirectional"))
      (node (ref "RN10") (pin "5") (pinfunction "2_5") (pintype "passive"))
    )
    (net (code "132") (name "R6R") (class "Default")
      (node (ref "IC1") (pin "A6") (pinfunction "PT18B_A6") (pintype "bidirectional"))
      (node (ref "IC3") (pin "1") (pinfunction "I/O_1") (pintype "bidirectional"))
      (node (ref "RN10") (pin "3") (pinfunction "1_3") (pintype "passive"))
      (node (ref "RN27") (pin "3") (pinfunction "1_3") (pintype "passive"))
      (node (ref "RN9") (pin "2") (pinfunction "1_2") (pintype "passive"))
    )
    (net (code "133") (name "R6T") (class "Default")
      (node (ref "IC1") (pin "A7") (pinfunction "PT29A_A7") (pintype "bidirectional"))
      (node (ref "RN10") (pin "6") (pinfunction "2_6") (pintype "passive"))
    )
    (net (code "134") (name "R7R") (class "Default")
      (node (ref "IC1") (pin "B9") (pinfunction "PT38A_B9") (pintype "bidirectional"))
      (node (ref "IC3") (pin "4") (pinfunction "I/O3_4") (pintype "bidirectional"))
      (node (ref "RN10") (pin "2") (pinfunction "1_2") (pintype "passive"))
      (node (ref "RN27") (pin "2") (pinfunction "1_2") (pintype "passive"))
      (node (ref "RN9") (pin "3") (pinfunction "1_3") (pintype "passive"))
    )
    (net (code "135") (name "R7T") (class "Default")
      (node (ref "IC1") (pin "B8") (pinfunction "PT35B_B8") (pintype "bidirectional"))
      (node (ref "RN10") (pin "7") (pinfunction "2_7") (pintype "passive"))
    )
    (net (code "136") (name "R8R") (class "Default")
      (node (ref "IC1") (pin "A9") (pinfunction "PT42A_A9") (pintype "bidirectional"))
      (node (ref "IC3") (pin "6") (pinfunction "I/O4_6") (pintype "bidirectional"))
      (node (ref "RN10") (pin "1") (pinfunction "1_1") (pintype "passive"))
      (node (ref "RN27") (pin "1") (pinfunction "1_1") (pintype "passive"))
      (node (ref "RN9") (pin "4") (pinfunction "1_4") (pintype "passive"))
    )
    (net (code "137") (name "R8T") (class "Default")
      (node (ref "IC1") (pin "A8") (pinfunction "PT29B_A8") (pintype "bidirectional"))
      (node (ref "RN10") (pin "8") (pinfunction "2_8") (pintype "passive"))
    )
    (net (code "138") (name "R9R") (class "Default")
      (node (ref "IC1") (pin "C9") (pinfunction "PT38B_C9") (pintype "bidirectional"))
      (node (ref "IC4") (pin "4") (pinfunction "I/O3_4") (pintype "bidirectional"))
      (node (ref "RN11") (pin "1") (pinfunction "1_1") (pintype "passive"))
      (node (ref "RN2") (pin "4") (pinfunction "1_4") (pintype "passive"))
      (node (ref "RN26") (pin "4") (pinfunction "1_4") (pintype "passive"))
    )
    (net (code "139") (name "R9T") (class "Default")
      (node (ref "IC1") (pin "B10") (pinfunction "PT44A_B10") (pintype "bidirectional"))
      (node (ref "RN2") (pin "5") (pinfunction "2_5") (pintype "passive"))
    )
    (net (code "140") (name "R10R") (class "Default")
      (node (ref "IC1") (pin "A10") (pinfunction "PT42B_A10") (pintype "bidirectional"))
      (node (ref "IC4") (pin "6") (pinfunction "I/O4_6") (pintype "bidirectional"))
      (node (ref "RN11") (pin "2") (pinfunction "1_2") (pintype "passive"))
      (node (ref "RN2") (pin "3") (pinfunction "1_3") (pintype "passive"))
      (node (ref "RN26") (pin "3") (pinfunction "1_3") (pintype "passive"))
    )
    (net (code "141") (name "R10T") (class "Default")
      (node (ref "IC1") (pin "A11") (pinfunction "PT53A_A11") (pintype "bidirectional"))
      (node (ref "RN2") (pin "6") (pinfunction "2_6") (pintype "passive"))
    )
    (net (code "142") (name "R11R") (class "Default")
      (node (ref "IC1") (pin "B12") (pinfunction "PT56A_B12") (pintype "bidirectional"))
      (node (ref "IC4") (pin "3") (pinfunction "I/O2_3") (pintype "bidirectional"))
      (node (ref "RN11") (pin "3") (pinfunction "1_3") (pintype "passive"))
      (node (ref "RN2") (pin "2") (pinfunction "1_2") (pintype "passive"))
      (node (ref "RN26") (pin "2") (pinfunction "1_2") (pintype "passive"))
    )
    (net (code "143") (name "R11T") (class "Default")
      (node (ref "IC1") (pin "B11") (pinfunction "PT49A_B11") (pintype "bidirectional"))
      (node (ref "RN2") (pin "7") (pinfunction "2_7") (pintype "passive"))
    )
    (net (code "144") (name "R12R") (class "Default")
      (node (ref "IC1") (pin "A13") (pinfunction "PT65A_A13") (pintype "bidirectional"))
      (node (ref "IC4") (pin "1") (pinfunction "I/O_1") (pintype "bidirectional"))
      (node (ref "RN11") (pin "4") (pinfunction "1_4") (pintype "passive"))
      (node (ref "RN2") (pin "1") (pinfunction "1_1") (pintype "passive"))
      (node (ref "RN26") (pin "1") (pinfunction "1_1") (pintype "passive"))
    )
    (net (code "145") (name "R12T") (class "Default")
      (node (ref "IC1") (pin "A12") (pinfunction "PT53B_A12") (pintype "bidirectional"))
      (node (ref "RN2") (pin "8") (pinfunction "2_8") (pintype "passive"))
    )
    (net (code "146") (name "R13R") (class "Default")
      (node (ref "IC1") (pin "B13") (pinfunction "PT60A_B13") (pintype "bidirectional"))
      (node (ref "IC5") (pin "3") (pinfunction "I/O2_3") (pintype "bidirectional"))
      (node (ref "RN12") (pin "1") (pinfunction "1_1") (pintype "passive"))
      (node (ref "RN25") (pin "4") (pinfunction "1_4") (pintype "passive"))
      (node (ref "RN3") (pin "4") (pinfunction "1_4") (pintype "passive"))
    )
    (net (code "147") (name "R13T") (class "Default")
      (node (ref "IC1") (pin "B14") (pinfunction "PT67A_B14") (pintype "bidirectional"))
      (node (ref "RN3") (pin "5") (pinfunction "2_5") (pintype "passive"))
    )
    (net (code "148") (name "R14R") (class "Default")
      (node (ref "IC1") (pin "A14") (pinfunction "PT65B_A14") (pintype "bidirectional"))
      (node (ref "IC5") (pin "1") (pinfunction "I/O_1") (pintype "bidirectional"))
      (node (ref "RN12") (pin "2") (pinfunction "1_2") (pintype "passive"))
      (node (ref "RN25") (pin "3") (pinfunction "1_3") (pintype "passive"))
      (node (ref "RN3") (pin "3") (pinfunction "1_3") (pintype "passive"))
    )
    (net (code "149") (name "R14T") (class "Default")
      (node (ref "IC1") (pin "A15") (pinfunction "PT67B_A15") (pintype "bidirectional"))
      (node (ref "RN3") (pin "6") (pinfunction "2_6") (pintype "passive"))
    )
    (net (code "150") (name "R15R") (class "Default")
      (node (ref "IC1") (pin "C15") (pinfunction "PR5B_C15") (pintype "bidirectional"))
      (node (ref "IC5") (pin "4") (pinfunction "I/O3_4") (pintype "bidirectional"))
      (node (ref "RN12") (pin "3") (pinfunction "1_3") (pintype "passive"))
      (node (ref "RN25") (pin "2") (pinfunction "1_2") (pintype "passive"))
      (node (ref "RN3") (pin "2") (pinfunction "1_2") (pintype "passive"))
    )
    (net (code "151") (name "R15T") (class "Default")
      (node (ref "IC1") (pin "B16") (pinfunction "PR2A_B16") (pintype "bidirectional"))
      (node (ref "RN3") (pin "7") (pinfunction "2_7") (pintype "passive"))
    )
    (net (code "152") (name "R16R") (class "Default")
      (node (ref "IC1") (pin "D16") (pinfunction "PR8A_D16") (pintype "bidirectional"))
      (node (ref "IC5") (pin "6") (pinfunction "I/O4_6") (pintype "bidirectional"))
      (node (ref "RN12") (pin "4") (pinfunction "1_4") (pintype "passive"))
      (node (ref "RN25") (pin "1") (pinfunction "1_1") (pintype "passive"))
      (node (ref "RN3") (pin "1") (pinfunction "1_1") (pintype "passive"))
    )
    (net (code "153") (name "R16T") (class "Default")
      (node (ref "IC1") (pin "C16") (pinfunction "PR5A_C16") (pintype "bidirectional"))
      (node (ref "RN3") (pin "8") (pinfunction "2_8") (pintype "passive"))
    )
    (net (code "154") (name "SCL") (class "Default")
      (node (ref "IC1") (pin "P5") (pinfunction "PL47D_P5") (pintype "bidirectional"))
      (node (ref "IC11") (pin "6") (pinfunction "SCL_6") (pintype "bidirectional"))
      (node (ref "IC12") (pin "5") (pinfunction "SCL_5") (pintype "input"))
      (node (ref "U15") (pin "13") (pinfunction "AP_SCL/AP_SCLK_13") (pintype "input"))
    )
    (net (code "155") (name "SDA") (class "Default")
      (node (ref "IC1") (pin "R5") (pinfunction "PL44A_R5") (pintype "bidirectional"))
      (node (ref "IC11") (pin "7") (pinfunction "SDA_7") (pintype "bidirectional"))
      (node (ref "IC12") (pin "6") (pinfunction "SDA_6") (pintype "bidirectional"))
      (node (ref "U15") (pin "14") (pinfunction "AP_SDA/AP_SDIO/AP_SDI_14") (pintype "bidirectional"))
    )
    (net (code "156") (name "SELFRESET") (class "Default")
      (node (ref "IC1") (pin "T6") (pinfunction "PB4A_T6") (pintype "bidirectional"))
      (node (ref "JP2") (pin "1") (pinfunction "1_1") (pintype "passive"))
    )
    (net (code "157") (name "SWITCH") (class "Default")
      (node (ref "IC11") (pin "1") (pinfunction "IO0_1") (pintype "bidirectional"))
      (node (ref "R29") (pin "2") (pinfunction "2_2") (pintype "passive"))
      (node (ref "R31") (pin "2") (pinfunction "2_2") (pintype "passive"))
      (node (ref "S1") (pin "1") (pinfunction "1_1") (pintype "passive"))
    )
    (net (code "158") (name "T1") (class "Default")
      (node (ref "IC1") (pin "M1") (pinfunction "PL26C_M1") (pintype "bidirectional"))
      (node (ref "RN7") (pin "1") (pinfunction "1_1") (pintype "passive"))
    )
    (net (code "159") (name "T2") (class "Default")
      (node (ref "IC1") (pin "L3") (pinfunction "PL32C_L3") (pintype "bidirectional"))
      (node (ref "RN7") (pin "2") (pinfunction "1_2") (pintype "passive"))
    )
    (net (code "160") (name "T3") (class "Default")
      (node (ref "IC1") (pin "L1") (pinfunction "PL26A_L1") (pintype "bidirectional"))
      (node (ref "RN7") (pin "3") (pinfunction "1_3") (pintype "passive"))
    )
    (net (code "161") (name "T4") (class "Default")
      (node (ref "IC1") (pin "L2") (pinfunction "PL26B_L2") (pintype "bidirectional"))
      (node (ref "RN7") (pin "4") (pinfunction "1_4") (pintype "passive"))
    )
    (net (code "162") (name "T5") (class "Default")
      (node (ref "IC1") (pin "K1") (pinfunction "PL23C_K1") (pintype "bidirectional"))
      (node (ref "RN6") (pin "1") (pinfunction "1_1") (pintype "passive"))
    )
    (net (code "163") (name "T6") (class "Default")
      (node (ref "IC1") (pin "K2") (pinfunction "PL23D_K2") (pintype "bidirectional"))
      (node (ref "RN6") (pin "2") (pinfunction "1_2") (pintype "passive"))
    )
    (net (code "164") (name "T7") (class "Default")
      (node (ref "IC1") (pin "J1") (pinfunction "PL23A_J1") (pintype "bidirectional"))
      (node (ref "RN6") (pin "3") (pinfunction "1_3") (pintype "passive"))
    )
    (net (code "165") (name "T8") (class "Default")
      (node (ref "IC1") (pin "J2") (pinfunction "PL23B_J2") (pintype "bidirectional"))
      (node (ref "RN6") (pin "4") (pinfunction "1_4") (pintype "passive"))
    )
    (net (code "166") (name "T9") (class "Default")
      (node (ref "IC1") (pin "G1") (pinfunction "PL20A_G1") (pintype "bidirectional"))
      (node (ref "RN5") (pin "1") (pinfunction "1_1") (pintype "passive"))
    )
    (net (code "167") (name "T10") (class "Default")
      (node (ref "IC1") (pin "F2") (pinfunction "PL11C_F2") (pintype "bidirectional"))
      (node (ref "RN5") (pin "2") (pinfunction "1_2") (pintype "passive"))
    )
    (net (code "168") (name "T11") (class "Default")
      (node (ref "IC1") (pin "F1") (pinfunction "PL14A_F1") (pintype "bidirectional"))
      (node (ref "RN5") (pin "3") (pinfunction "1_3") (pintype "passive"))
    )
    (net (code "169") (name "T12") (class "Default")
      (node (ref "IC1") (pin "E1") (pinfunction "PL11D_E1") (pintype "bidirectional"))
      (node (ref "RN5") (pin "4") (pinfunction "1_4") (pintype "passive"))
    )
    (net (code "170") (name "T13") (class "Default")
      (node (ref "IC1") (pin "E2") (pinfunction "PL8B_E2") (pintype "bidirectional"))
      (node (ref "RN4") (pin "1") (pinfunction "1_1") (pintype "passive"))
    )
    (net (code "171") (name "T14") (class "Default")
      (node (ref "IC1") (pin "D1") (pinfunction "PL8A_D1") (pintype "bidirectional"))
      (node (ref "RN4") (pin "2") (pinfunction "1_2") (pintype "passive"))
    )
    (net (code "172") (name "T15") (class "Default")
      (node (ref "IC1") (pin "C1") (pinfunction "PL5A_C1") (pintype "bidirectional"))
      (node (ref "RN4") (pin "3") (pinfunction "1_3") (pintype "passive"))
    )
    (net (code "173") (name "T16") (class "Default")
      (node (ref "IC1") (pin "B1") (pinfunction "PL2A_B1") (pintype "bidirectional"))
      (node (ref "RN4") (pin "4") (pinfunction "1_4") (pintype "passive"))
    )
    (net (code "174") (name "USB5V") (class "Default")
      (node (ref "C30") (pin "1") (pinfunction "1_1") (pintype "passive"))
      (node (ref "C35") (pin "1") (pinfunction "1_1") (pintype "passive"))
      (node (ref "IC10") (pin "1") (pinfunction "VIN_1") (pintype "bidirectional"))
      (node (ref "R25") (pin "2") (pinfunction "2_2") (pintype "passive"))
      (node (ref "U13") (pin "40") (pinfunction "VREGIN_40") (pintype "power_in"))
    )
    (net (code "175") (name "USBDN") (class "Default")
      (node (ref "J2") (pin "A7") (pinfunction "DN1_A7") (pintype "bidirectional"))
      (node (ref "J2") (pin "B7") (pinfunction "DN2_B7") (pintype "bidirectional"))
      (node (ref "U13") (pin "6") (pinfunction "DM_6") (pintype "bidirectional"))
    )
    (net (code "176") (name "USBDP") (class "Default")
      (node (ref "J2") (pin "A6") (pinfunction "DP1_A6") (pintype "bidirectional"))
      (node (ref "J2") (pin "B6") (pinfunction "DP2_B6") (pintype "bidirectional"))
      (node (ref "U13") (pin "7") (pinfunction "DP_7") (pintype "bidirectional"))
    )
    (net (code "177") (name "VBAT") (class "Default")
      (node (ref "C28") (pin "1") (pinfunction "1_1") (pintype "passive"))
      (node (ref "IC12") (pin "2") (pinfunction "IN-_2") (pintype "input"))
      (node (ref "JP1") (pin "4") (pinfunction "4_4") (pintype "passive"))
      (node (ref "R30") (pin "1") (pinfunction "1_1") (pintype "passive"))
      (node (ref "S1") (pin "3") (pinfunction "3_3") (pintype "passive"))
    )
    (net (code "178") (name "VCCAUX") (class "Default")
      (node (ref "C17") (pin "1") (pinfunction "1_1") (pintype "passive"))
      (node (ref "C8") (pin "1") (pinfunction "1_1") (pintype "passive"))
      (node (ref "IC1") (pin "G11") (pinfunction "VCCAUX_1_G11") (pintype "bidirectional"))
      (node (ref "IC1") (pin "K11") (pinfunction "VCCIO3_1_K11") (pintype "bidirectional"))
      (node (ref "IC1") (pin "L11") (pinfunction "VCCIO3_2_L11") (pintype "bidirectional"))
      (node (ref "IC1") (pin "L7") (pinfunction "VCCAUX_2_L7") (pintype "bidirectional"))
      (node (ref "U5") (pin "5") (pinfunction "VOUT_5") (pintype "output"))
    )
    (net (code "179") (name "VCHG") (class "Default")
      (node (ref "IC10") (pin "2") (pinfunction "VBAT_2") (pintype "bidirectional"))
      (node (ref "IC12") (pin "1") (pinfunction "IN+_1") (pintype "input"))
      (node (ref "R30") (pin "2") (pinfunction "2_2") (pintype "passive"))
    )
    (net (code "180") (name "VCLAMP") (class "Default")
      (node (ref "C26") (pin "1") (pinfunction "1_1") (pintype "passive"))
      (node (ref "D2") (pin "3") (pinfunction "C_3") (pintype "passive"))
      (node (ref "D4") (pin "C") (pinfunction "C_C") (pintype "passive"))
      (node (ref "IC2") (pin "2") (pinfunction "REF2_2") (pintype "input"))
      (node (ref "IC3") (pin "2") (pinfunction "REF2_2") (pintype "input"))
      (node (ref "IC4") (pin "2") (pinfunction "REF2_2") (pintype "input"))
      (node (ref "IC5") (pin "2") (pinfunction "REF2_2") (pintype "input"))
      (node (ref "Q2") (pin "1") (pinfunction "D_1_1") (pintype "bidirectional"))
      (node (ref "Q2") (pin "2") (pinfunction "D_2_2") (pintype "bidirectional"))
      (node (ref "Q2") (pin "5") (pinfunction "D_3_5") (pintype "bidirectional"))
      (node (ref "Q2") (pin "6") (pinfunction "D_4_6") (pintype "bidirectional"))
      (node (ref "R4") (pin "1") (pinfunction "1_1") (pintype "passive"))
    )
    (net (code "181") (name "VNRF") (class "Default")
      (node (ref "C18") (pin "1") (pinfunction "1_1") (pintype "passive"))
      (node (ref "C19") (pin "1") (pinfunction "1_1") (pintype "passive"))
      (node (ref "JP1") (pin "5") (pinfunction "5_5") (pintype "passive"))
      (node (ref "U$9") (pin "3V3") (pinfunction "3V3_3V3") (pintype "bidirectional"))
      (node (ref "U14") (pin "5") (pinfunction "VOUT_5") (pintype "output"))
      (node (ref "U15") (pin "12") (pinfunction "AP_CS_12") (pintype "input"))
      (node (ref "U15") (pin "5") (pinfunction "VDDIO_5") (pintype "power_in"))
      (node (ref "U15") (pin "8") (pinfunction "VDD_8") (pintype "power_in"))
    )
    (net (code "182") (name "VSYS") (class "Default")
      (node (ref "C16") (pin "1") (pinfunction "1_1") (pintype "passive"))
      (node (ref "IC10") (pin "10") (pinfunction "VOUT_10") (pintype "bidirectional"))
      (node (ref "IC11") (pin "8") (pinfunction "VDD_8") (pintype "bidirectional"))
      (node (ref "IC12") (pin "4") (pinfunction "VS_4") (pintype "power_in"))
      (node (ref "JP3") (pin "1") (pinfunction "1_1") (pintype "passive"))
      (node (ref "R10") (pin "1") (pinfunction "1_1") (pintype "passive"))
      (node (ref "R11") (pin "1") (pinfunction "1_1") (pintype "passive"))
      (node (ref "R15") (pin "1") (pinfunction "1_1") (pintype "passive"))
      (node (ref "R4") (pin "2") (pinfunction "2_2") (pintype "passive"))
      (node (ref "R5") (pin "1") (pinfunction "1_1") (pintype "passive"))
      (node (ref "R6") (pin "1") (pinfunction "1_1") (pintype "passive"))
      (node (ref "R7") (pin "2") (pinfunction "2_2") (pintype "passive"))
    )
    (net (code "183") (name "VTX") (class "Default")
      (node (ref "C13") (pin "1") (pinfunction "1_1") (pintype "passive"))
      (node (ref "C22") (pin "1") (pinfunction "1_1") (pintype "passive"))
      (node (ref "C23") (pin "1") (pinfunction "1_1") (pintype "passive"))
      (node (ref "R9") (pin "1") (pinfunction "1_1") (pintype "passive"))
      (node (ref "U1") (pin "8") (pinfunction "VCC_8") (pintype "power_in"))
      (node (ref "U10") (pin "8") (pinfunction "VCC_8") (pintype "power_in"))
      (node (ref "U11") (pin "8") (pinfunction "VCC_8") (pintype "power_in"))
      (node (ref "U12") (pin "8") (pinfunction "VCC_8") (pintype "power_in"))
      (node (ref "U3") (pin "8") (pinfunction "VCC_8") (pintype "power_in"))
      (node (ref "U7") (pin "8") (pinfunction "VCC_8") (pintype "power_in"))
      (node (ref "U8") (pin "8") (pinfunction "VCC_8") (pintype "power_in"))
      (node (ref "U9") (pin "8") (pinfunction "VCC_8") (pintype "power_in"))
    )
    (net (code "184") (name "VTXZ") (class "Default")
      (node (ref "C3") (pin "1") (pinfunction "1_1") (pintype "passive"))
      (node (ref "D1") (pin "C") (pinfunction "C_C") (pintype "passive"))
      (node (ref "R3") (pin "2") (pinfunction "2_2") (pintype "passive"))
      (node (ref "R9") (pin "2") (pinfunction "2_2") (pintype "passive"))
    )
    (net (code "185") (name "unconnected-(IC1-DONE-PadP9)") (class "Default")
      (node (ref "IC1") (pin "P9") (pinfunction "DONE_P9") (pintype "bidirectional"))
    )
    (net (code "186") (name "unconnected-(IC1-PB4B-PadR6)") (class "Default")
      (node (ref "IC1") (pin "R6") (pinfunction "PB4B_R6") (pintype "bidirectional"))
    )
    (net (code "187") (name "unconnected-(IC1-PB6A-PadR7)") (class "Default")
      (node (ref "IC1") (pin "R7") (pinfunction "PB6A_R7") (pintype "bidirectional"))
    )
    (net (code "188") (name "unconnected-(IC1-PB6B-PadP7)") (class "Default")
      (node (ref "IC1") (pin "P7") (pinfunction "PB6B_P7") (pintype "bidirectional"))
    )
    (net (code "189") (name "unconnected-(IC1-PB9A-PadN7)") (class "Default")
      (node (ref "IC1") (pin "N7") (pinfunction "PB9A_N7") (pintype "bidirectional"))
    )
    (net (code "190") (name "unconnected-(IC1-PB9B-PadM7)") (class "Default")
      (node (ref "IC1") (pin "M7") (pinfunction "PB9B_M7") (pintype "bidirectional"))
    )
    (net (code "191") (name "unconnected-(IC1-PB13A-PadR8)") (class "Default")
      (node (ref "IC1") (pin "R8") (pinfunction "PB13A_R8") (pintype "bidirectional"))
    )
    (net (code "192") (name "unconnected-(IC1-PB13B-PadP8)") (class "Default")
      (node (ref "IC1") (pin "P8") (pinfunction "PB13B_P8") (pintype "bidirectional"))
    )
    (net (code "193") (name "unconnected-(IC1-PB15B-PadM8)") (class "Default")
      (node (ref "IC1") (pin "M8") (pinfunction "PB15B_M8") (pintype "bidirectional"))
    )
    (net (code "194") (name "unconnected-(IC1-PB18A-PadM9)") (class "Default")
      (node (ref "IC1") (pin "M9") (pinfunction "PB18A_M9") (pintype "bidirectional"))
    )
    (net (code "195") (name "unconnected-(IC1-PL2B-PadB2)") (class "Default")
      (node (ref "IC1") (pin "B2") (pinfunction "PL2B_B2") (pintype "bidirectional"))
    )
    (net (code "196") (name "unconnected-(IC1-PL2C-PadC3)") (class "Default")
      (node (ref "IC1") (pin "C3") (pinfunction "PL2C_C3") (pintype "bidirectional"))
    )
    (net (code "197") (name "unconnected-(IC1-PL2D-PadD3)") (class "Default")
      (node (ref "IC1") (pin "D3") (pinfunction "PL2D_D3") (pintype "bidirectional"))
    )
    (net (code "198") (name "unconnected-(IC1-PL5B-PadC2)") (class "Default")
      (node (ref "IC1") (pin "C2") (pinfunction "PL5B_C2") (pintype "bidirectional"))
    )
    (net (code "199") (name "unconnected-(IC1-PL5C-PadE3)") (class "Default")
      (node (ref "IC1") (pin "E3") (pinfunction "PL5C_E3") (pintype "bidirectional"))
    )
    (net (code "200") (name "unconnected-(IC1-PL5D-PadF3)") (class "Default")
      (node (ref "IC1") (pin "F3") (pinfunction "PL5D_F3") (pintype "bidirectional"))
    )
    (net (code "201") (name "unconnected-(IC1-PL8C-PadF4)") (class "Default")
      (node (ref "IC1") (pin "F4") (pinfunction "PL8C_F4") (pintype "bidirectional"))
    )
    (net (code "202") (name "unconnected-(IC1-PL8D-PadF5)") (class "Default")
      (node (ref "IC1") (pin "F5") (pinfunction "PL8D_F5") (pintype "bidirectional"))
    )
    (net (code "203") (name "unconnected-(IC1-PL11A-PadG5)") (class "Default")
      (node (ref "IC1") (pin "G5") (pinfunction "PL11A_G5") (pintype "bidirectional"))
    )
    (net (code "204") (name "unconnected-(IC1-PL11B-PadG4)") (class "Default")
      (node (ref "IC1") (pin "G4") (pinfunction "PL11B_G4") (pintype "bidirectional"))
    )
    (net (code "205") (name "unconnected-(IC1-PL14B-PadG2)") (class "Default")
      (node (ref "IC1") (pin "G2") (pinfunction "PL14B_G2") (pintype "bidirectional"))
    )
    (net (code "206") (name "unconnected-(IC1-PL14C-PadG3)") (class "Default")
      (node (ref "IC1") (pin "G3") (pinfunction "PL14C_G3") (pintype "bidirectional"))
    )
    (net (code "207") (name "unconnected-(IC1-PL14D-PadH3)") (class "Default")
      (node (ref "IC1") (pin "H3") (pinfunction "PL14D_H3") (pintype "bidirectional"))
    )
    (net (code "208") (name "unconnected-(IC1-PL17A-PadH5)") (class "Default")
      (node (ref "IC1") (pin "H5") (pinfunction "PL17A_H5") (pintype "bidirectional"))
    )
    (net (code "209") (name "unconnected-(IC1-PL17B-PadH4)") (class "Default")
      (node (ref "IC1") (pin "H4") (pinfunction "PL17B_H4") (pintype "bidirectional"))
    )
    (net (code "210") (name "unconnected-(IC1-PL17C-PadJ4)") (class "Default")
      (node (ref "IC1") (pin "J4") (pinfunction "PL17C_J4") (pintype "bidirectional"))
    )
    (net (code "211") (name "unconnected-(IC1-PL17D-PadJ5)") (class "Default")
      (node (ref "IC1") (pin "J5") (pinfunction "PL17D_J5") (pintype "bidirectional"))
    )
    (net (code "212") (name "unconnected-(IC1-PL20B-PadH2)") (class "Default")
      (node (ref "IC1") (pin "H2") (pinfunction "PL20B_H2") (pintype "bidirectional"))
    )
    (net (code "213") (name "unconnected-(IC1-PL20C-PadJ3)") (class "Default")
      (node (ref "IC1") (pin "J3") (pinfunction "PL20C_J3") (pintype "bidirectional"))
    )
    (net (code "214") (name "unconnected-(IC1-PL20D-PadK3)") (class "Default")
      (node (ref "IC1") (pin "K3") (pinfunction "PL20D_K3") (pintype "bidirectional"))
    )
    (net (code "215") (name "unconnected-(IC1-PL29A-PadK4)") (class "Default")
      (node (ref "IC1") (pin "K4") (pinfunction "PL29A_K4") (pintype "bidirectional"))
    )
    (net (code "216") (name "unconnected-(IC1-PL29B-PadK5)") (class "Default")
      (node (ref "IC1") (pin "K5") (pinfunction "PL29B_K5") (pintype "bidirectional"))
    )
    (net (code "217") (name "unconnected-(IC1-PL29C-PadL4)") (class "Default")
      (node (ref "IC1") (pin "L4") (pinfunction "PL29C_L4") (pintype "bidirectional"))
    )
    (net (code "218") (name "unconnected-(IC1-PL29D-PadL5)") (class "Default")
      (node (ref "IC1") (pin "L5") (pinfunction "PL29D_L5") (pintype "bidirectional"))
    )
    (net (code "219") (name "unconnected-(IC1-PL32A-PadN1)") (class "Default")
      (node (ref "IC1") (pin "N1") (pinfunction "PL32A_N1") (pintype "bidirectional"))
    )
    (net (code "220") (name "unconnected-(IC1-PL32B-PadP2)") (class "Default")
      (node (ref "IC1") (pin "P2") (pinfunction "PL32B_P2") (pintype "bidirectional"))
    )
    (net (code "221") (name "unconnected-(IC1-PL32D-PadM3)") (class "Default")
      (node (ref "IC1") (pin "M3") (pinfunction "PL32D_M3") (pintype "bidirectional"))
    )
    (net (code "222") (name "unconnected-(IC1-PL35A-PadP1)") (class "Default")
      (node (ref "IC1") (pin "P1") (pinfunction "PL35A_P1") (pintype "bidirectional"))
    )
    (net (code "223") (name "unconnected-(IC1-PL35C-PadM4)") (class "Default")
      (node (ref "IC1") (pin "M4") (pinfunction "PL35C_M4") (pintype "bidirectional"))
    )
    (net (code "224") (name "unconnected-(IC1-PL35D-PadN3)") (class "Default")
      (node (ref "IC1") (pin "N3") (pinfunction "PL35D_N3") (pintype "bidirectional"))
    )
    (net (code "225") (name "unconnected-(IC1-PL38A-PadN4)") (class "Default")
      (node (ref "IC1") (pin "N4") (pinfunction "PL38A_N4") (pintype "bidirectional"))
    )
    (net (code "226") (name "unconnected-(IC1-PL38B-PadP3)") (class "Default")
      (node (ref "IC1") (pin "P3") (pinfunction "PL38B_P3") (pintype "bidirectional"))
    )
    (net (code "227") (name "unconnected-(IC1-PL41A-PadP4)") (class "Default")
      (node (ref "IC1") (pin "P4") (pinfunction "PL41A_P4") (pintype "bidirectional"))
    )
    (net (code "228") (name "unconnected-(IC1-PL44C-PadM5)") (class "Default")
      (node (ref "IC1") (pin "M5") (pinfunction "PL44C_M5") (pintype "bidirectional"))
    )
    (net (code "229") (name "unconnected-(IC1-PL44D-PadN5)") (class "Default")
      (node (ref "IC1") (pin "N5") (pinfunction "PL44D_N5") (pintype "bidirectional"))
    )
    (net (code "230") (name "unconnected-(IC1-PL47A-PadM6)") (class "Default")
      (node (ref "IC1") (pin "M6") (pinfunction "PL47A_M6") (pintype "bidirectional"))
    )
    (net (code "231") (name "unconnected-(IC1-PL47B-PadN6)") (class "Default")
      (node (ref "IC1") (pin "N6") (pinfunction "PL47B_N6") (pintype "bidirectional"))
    )
    (net (code "232") (name "unconnected-(IC1-PR2B-PadB15)") (class "Default")
      (node (ref "IC1") (pin "B15") (pinfunction "PR2B_B15") (pintype "bidirectional"))
    )
    (net (code "233") (name "unconnected-(IC1-PR2C-PadC14)") (class "Default")
      (node (ref "IC1") (pin "C14") (pinfunction "PR2C_C14") (pintype "bidirectional"))
    )
    (net (code "234") (name "unconnected-(IC1-PR2D-PadD14)") (class "Default")
      (node (ref "IC1") (pin "D14") (pinfunction "PR2D_D14") (pintype "bidirectional"))
    )
    (net (code "235") (name "unconnected-(IC1-PR5C-PadE14)") (class "Default")
      (node (ref "IC1") (pin "E14") (pinfunction "PR5C_E14") (pintype "bidirectional"))
    )
    (net (code "236") (name "unconnected-(IC1-PR5D-PadF14)") (class "Default")
      (node (ref "IC1") (pin "F14") (pinfunction "PR5D_F14") (pintype "bidirectional"))
    )
    (net (code "237") (name "unconnected-(IC1-PR8B-PadE15)") (class "Default")
      (node (ref "IC1") (pin "E15") (pinfunction "PR8B_E15") (pintype "bidirectional"))
    )
    (net (code "238") (name "unconnected-(IC1-PR8C-PadF13)") (class "Default")
      (node (ref "IC1") (pin "F13") (pinfunction "PR8C_F13") (pintype "bidirectional"))
    )
    (net (code "239") (name "unconnected-(IC1-PR8D-PadF12)") (class "Default")
      (node (ref "IC1") (pin "F12") (pinfunction "PR8D_F12") (pintype "bidirectional"))
    )
    (net (code "240") (name "unconnected-(IC1-PR11A-PadG12)") (class "Default")
      (node (ref "IC1") (pin "G12") (pinfunction "PR11A_G12") (pintype "bidirectional"))
    )
    (net (code "241") (name "unconnected-(IC1-PR11B-PadG13)") (class "Default")
      (node (ref "IC1") (pin "G13") (pinfunction "PR11B_G13") (pintype "bidirectional"))
    )
    (net (code "242") (name "unconnected-(IC1-PR11C-PadF15)") (class "Default")
      (node (ref "IC1") (pin "F15") (pinfunction "PR11C_F15") (pintype "bidirectional"))
    )
    (net (code "243") (name "unconnected-(IC1-PR11D-PadE16)") (class "Default")
      (node (ref "IC1") (pin "E16") (pinfunction "PR11D_E16") (pintype "bidirectional"))
    )
    (net (code "244") (name "unconnected-(IC1-PR14A-PadF16)") (class "Default")
      (node (ref "IC1") (pin "F16") (pinfunction "PR14A_F16") (pintype "bidirectional"))
    )
    (net (code "245") (name "unconnected-(IC1-PR14B-PadG15)") (class "Default")
      (node (ref "IC1") (pin "G15") (pinfunction "PR14B_G15") (pintype "bidirectional"))
    )
    (net (code "246") (name "unconnected-(IC1-PR14C-PadG14)") (class "Default")
      (node (ref "IC1") (pin "G14") (pinfunction "PR14C_G14") (pintype "bidirectional"))
    )
    (net (code "247") (name "unconnected-(IC1-PR14D-PadH14)") (class "Default")
      (node (ref "IC1") (pin "H14") (pinfunction "PR14D_H14") (pintype "bidirectional"))
    )
    (net (code "248") (name "unconnected-(IC1-PR17A-PadH12)") (class "Default")
      (node (ref "IC1") (pin "H12") (pinfunction "PR17A_H12") (pintype "bidirectional"))
    )
    (net (code "249") (name "unconnected-(IC1-PR17B-PadH13)") (class "Default")
      (node (ref "IC1") (pin "H13") (pinfunction "PR17B_H13") (pintype "bidirectional"))
    )
    (net (code "250") (name "unconnected-(IC1-PR17C-PadJ13)") (class "Default")
      (node (ref "IC1") (pin "J13") (pinfunction "PR17C_J13") (pintype "bidirectional"))
    )
    (net (code "251") (name "unconnected-(IC1-PR17D-PadJ12)") (class "Default")
      (node (ref "IC1") (pin "J12") (pinfunction "PR17D_J12") (pintype "bidirectional"))
    )
    (net (code "252") (name "unconnected-(IC1-PR20A-PadG16)") (class "Default")
      (node (ref "IC1") (pin "G16") (pinfunction "PR20A_G16") (pintype "bidirectional"))
    )
    (net (code "253") (name "unconnected-(IC1-PR20B-PadH15)") (class "Default")
      (node (ref "IC1") (pin "H15") (pinfunction "PR20B_H15") (pintype "bidirectional"))
    )
    (net (code "254") (name "unconnected-(IC1-PR20C-PadJ14)") (class "Default")
      (node (ref "IC1") (pin "J14") (pinfunction "PR20C_J14") (pintype "bidirectional"))
    )
    (net (code "255") (name "unconnected-(IC1-PR20D-PadK14)") (class "Default")
      (node (ref "IC1") (pin "K14") (pinfunction "PR20D_K14") (pintype "bidirectional"))
    )
    (net (code "256") (name "unconnected-(IC1-PR23A-PadJ16)") (class "Default")
      (node (ref "IC1") (pin "J16") (pinfunction "PR23A_J16") (pintype "bidirectional"))
    )
    (net (code "257") (name "unconnected-(IC1-PR23B-PadJ15)") (class "Default")
      (node (ref "IC1") (pin "J15") (pinfunction "PR23B_J15") (pintype "bidirectional"))
    )
    (net (code "258") (name "unconnected-(IC1-PR23C-PadK16)") (class "Default")
      (node (ref "IC1") (pin "K16") (pinfunction "PR23C_K16") (pintype "bidirectional"))
    )
    (net (code "259") (name "unconnected-(IC1-PR23D-PadK15)") (class "Default")
      (node (ref "IC1") (pin "K15") (pinfunction "PR23D_K15") (pintype "bidirectional"))
    )
    (net (code "260") (name "unconnected-(IC1-PR26A-PadL16)") (class "Default")
      (node (ref "IC1") (pin "L16") (pinfunction "PR26A_L16") (pintype "bidirectional"))
    )
    (net (code "261") (name "unconnected-(IC1-PR26B-PadL15)") (class "Default")
      (node (ref "IC1") (pin "L15") (pinfunction "PR26B_L15") (pintype "bidirectional"))
    )
    (net (code "262") (name "unconnected-(IC1-PR26C-PadM16)") (class "Default")
      (node (ref "IC1") (pin "M16") (pinfunction "PR26C_M16") (pintype "bidirectional"))
    )
    (net (code "263") (name "unconnected-(IC1-PR26D-PadM15)") (class "Default")
      (node (ref "IC1") (pin "M15") (pinfunction "PR26D_M15") (pintype "bidirectional"))
    )
    (net (code "264") (name "unconnected-(IC1-PR29A-PadK13)") (class "Default")
      (node (ref "IC1") (pin "K13") (pinfunction "PR29A_K13") (pintype "bidirectional"))
    )
    (net (code "265") (name "unconnected-(IC1-PR29B-PadK12)") (class "Default")
      (node (ref "IC1") (pin "K12") (pinfunction "PR29B_K12") (pintype "bidirectional"))
    )
    (net (code "266") (name "unconnected-(IC1-PR29C-PadL13)") (class "Default")
      (node (ref "IC1") (pin "L13") (pinfunction "PR29C_L13") (pintype "bidirectional"))
    )
    (net (code "267") (name "unconnected-(IC1-PR29D-PadL12)") (class "Default")
      (node (ref "IC1") (pin "L12") (pinfunction "PR29D_L12") (pintype "bidirectional"))
    )
    (net (code "268") (name "unconnected-(IC1-PR32A-PadN16)") (class "Default")
      (node (ref "IC1") (pin "N16") (pinfunction "PR32A_N16") (pintype "bidirectional"))
    )
    (net (code "269") (name "unconnected-(IC1-PR32B-PadP15)") (class "Default")
      (node (ref "IC1") (pin "P15") (pinfunction "PR32B_P15") (pintype "bidirectional"))
    )
    (net (code "270") (name "unconnected-(IC1-PR32C-PadL14)") (class "Default")
      (node (ref "IC1") (pin "L14") (pinfunction "PR32C_L14") (pintype "bidirectional"))
    )
    (net (code "271") (name "unconnected-(IC1-PR32D-PadM14)") (class "Default")
      (node (ref "IC1") (pin "M14") (pinfunction "PR32D_M14") (pintype "bidirectional"))
    )
    (net (code "272") (name "unconnected-(IC1-PR35A-PadP16)") (class "Default")
      (node (ref "IC1") (pin "P16") (pinfunction "PR35A_P16") (pintype "bidirectional"))
    )
    (net (code "273") (name "unconnected-(IC1-PR35B-PadR16)") (class "Default")
      (node (ref "IC1") (pin "R16") (pinfunction "PR35B_R16") (pintype "bidirectional"))
    )
    (net (code "274") (name "unconnected-(IC1-PR35C-PadM13)") (class "Default")
      (node (ref "IC1") (pin "M13") (pinfunction "PR35C_M13") (pintype "bidirectional"))
    )
    (net (code "275") (name "unconnected-(IC1-PR35D-PadN14)") (class "Default")
      (node (ref "IC1") (pin "N14") (pinfunction "PR35D_N14") (pintype "bidirectional"))
    )
    (net (code "276") (name "unconnected-(IC1-PR38A-PadN13)") (class "Default")
      (node (ref "IC1") (pin "N13") (pinfunction "PR38A_N13") (pintype "bidirectional"))
    )
    (net (code "277") (name "unconnected-(IC1-PR38B-PadP14)") (class "Default")
      (node (ref "IC1") (pin "P14") (pinfunction "PR38B_P14") (pintype "bidirectional"))
    )
    (net (code "278") (name "unconnected-(IC1-PR38C-PadR15)") (class "Default")
      (node (ref "IC1") (pin "R15") (pinfunction "PR38C_R15") (pintype "bidirectional"))
    )
    (net (code "279") (name "unconnected-(IC1-PR38D-PadT15)") (class "Default")
      (node (ref "IC1") (pin "T15") (pinfunction "PR38D_T15") (pintype "bidirectional"))
    )
    (net (code "280") (name "unconnected-(IC1-PR41A-PadP13)") (class "Default")
      (node (ref "IC1") (pin "P13") (pinfunction "PR41A_P13") (pintype "bidirectional"))
    )
    (net (code "281") (name "unconnected-(IC1-PR41B-PadR14)") (class "Default")
      (node (ref "IC1") (pin "R14") (pinfunction "PR41B_R14") (pintype "bidirectional"))
    )
    (net (code "282") (name "unconnected-(IC1-PR41C-PadR13)") (class "Default")
      (node (ref "IC1") (pin "R13") (pinfunction "PR41C_R13") (pintype "bidirectional"))
    )
    (net (code "283") (name "unconnected-(IC1-PR41D-PadT14)") (class "Default")
      (node (ref "IC1") (pin "T14") (pinfunction "PR41D_T14") (pintype "bidirectional"))
    )
    (net (code "284") (name "unconnected-(IC1-PR44A-PadR12)") (class "Default")
      (node (ref "IC1") (pin "R12") (pinfunction "PR44A_R12") (pintype "bidirectional"))
    )
    (net (code "285") (name "unconnected-(IC1-PR44B-PadT13)") (class "Default")
      (node (ref "IC1") (pin "T13") (pinfunction "PR44B_T13") (pintype "bidirectional"))
    )
    (net (code "286") (name "unconnected-(IC1-PR44C-PadM12)") (class "Default")
      (node (ref "IC1") (pin "M12") (pinfunction "PR44C_M12") (pintype "bidirectional"))
    )
    (net (code "287") (name "unconnected-(IC1-PR44D-PadN12)") (class "Default")
      (node (ref "IC1") (pin "N12") (pinfunction "PR44D_N12") (pintype "bidirectional"))
    )
    (net (code "288") (name "unconnected-(IC1-PR47A-PadM11)") (class "Default")
      (node (ref "IC1") (pin "M11") (pinfunction "PR47A_M11") (pintype "bidirectional"))
    )
    (net (code "289") (name "unconnected-(IC1-PR47B-PadN11)") (class "Default")
      (node (ref "IC1") (pin "N11") (pinfunction "PR47B_N11") (pintype "bidirectional"))
    )
    (net (code "290") (name "unconnected-(IC1-PR47C-PadP11)") (class "Default")
      (node (ref "IC1") (pin "P11") (pinfunction "PR47C_P11") (pintype "bidirectional"))
    )
    (net (code "291") (name "unconnected-(IC1-PR47D-PadP12)") (class "Default")
      (node (ref "IC1") (pin "P12") (pinfunction "PR47D_P12") (pintype "bidirectional"))
    )
    (net (code "292") (name "unconnected-(IC1-PT9A-PadE4)") (class "Default")
      (node (ref "IC1") (pin "E4") (pinfunction "PT9A_E4") (pintype "bidirectional"))
    )
    (net (code "293") (name "unconnected-(IC1-PT9B-PadD4)") (class "Default")
      (node (ref "IC1") (pin "D4") (pinfunction "PT9B_D4") (pintype "bidirectional"))
    )
    (net (code "294") (name "unconnected-(IC1-PT11A-PadC4)") (class "Default")
      (node (ref "IC1") (pin "C4") (pinfunction "PT11A_C4") (pintype "bidirectional"))
    )
    (net (code "295") (name "unconnected-(IC1-PT13A-PadE5)") (class "Default")
      (node (ref "IC1") (pin "E5") (pinfunction "PT13A_E5") (pintype "bidirectional"))
    )
    (net (code "296") (name "unconnected-(IC1-PT13B-PadD5)") (class "Default")
      (node (ref "IC1") (pin "D5") (pinfunction "PT13B_D5") (pintype "bidirectional"))
    )
    (net (code "297") (name "unconnected-(IC1-PT20A-PadE6)") (class "Default")
      (node (ref "IC1") (pin "E6") (pinfunction "PT20A_E6") (pintype "bidirectional"))
    )
    (net (code "298") (name "unconnected-(IC1-PT20B-PadD6)") (class "Default")
      (node (ref "IC1") (pin "D6") (pinfunction "PT20B_D6") (pintype "bidirectional"))
    )
    (net (code "299") (name "unconnected-(IC1-PT22A-PadC6)") (class "Default")
      (node (ref "IC1") (pin "C6") (pinfunction "PT22A_C6") (pintype "bidirectional"))
    )
    (net (code "300") (name "unconnected-(IC1-PT24A-PadE7)") (class "Default")
      (node (ref "IC1") (pin "E7") (pinfunction "PT24A_E7") (pintype "bidirectional"))
    )
    (net (code "301") (name "unconnected-(IC1-PT24B-PadD7)") (class "Default")
      (node (ref "IC1") (pin "D7") (pinfunction "PT24B_D7") (pintype "bidirectional"))
    )
    (net (code "302") (name "unconnected-(IC1-PT27A-PadC7)") (class "Default")
      (node (ref "IC1") (pin "C7") (pinfunction "PT27A_C7") (pintype "bidirectional"))
    )
    (net (code "303") (name "unconnected-(IC1-PT33A-PadE8)") (class "Default")
      (node (ref "IC1") (pin "E8") (pinfunction "PT33A_E8") (pintype "bidirectional"))
    )
    (net (code "304") (name "unconnected-(IC1-PT33B-PadD8)") (class "Default")
      (node (ref "IC1") (pin "D8") (pinfunction "PT33B_D8") (pintype "bidirectional"))
    )
    (net (code "305") (name "unconnected-(IC1-PT35A-PadC8)") (class "Default")
      (node (ref "IC1") (pin "C8") (pinfunction "PT35A_C8") (pintype "bidirectional"))
    )
    (net (code "306") (name "unconnected-(IC1-PT40A-PadD9)") (class "Default")
      (node (ref "IC1") (pin "D9") (pinfunction "PT40A_D9") (pintype "bidirectional"))
    )
    (net (code "307") (name "unconnected-(IC1-PT40B-PadE9)") (class "Default")
      (node (ref "IC1") (pin "E9") (pinfunction "PT40B_E9") (pintype "bidirectional"))
    )
    (net (code "308") (name "unconnected-(IC1-PT44B-PadC10)") (class "Default")
      (node (ref "IC1") (pin "C10") (pinfunction "PT44B_C10") (pintype "bidirectional"))
    )
    (net (code "309") (name "unconnected-(IC1-PT47A-PadD10)") (class "Default")
      (node (ref "IC1") (pin "D10") (pinfunction "PT47A_D10") (pintype "bidirectional"))
    )
    (net (code "310") (name "unconnected-(IC1-PT47B-PadE10)") (class "Default")
      (node (ref "IC1") (pin "E10") (pinfunction "PT47B_E10") (pintype "bidirectional"))
    )
    (net (code "311") (name "unconnected-(IC1-PT49B-PadC11)") (class "Default")
      (node (ref "IC1") (pin "C11") (pinfunction "PT49B_C11") (pintype "bidirectional"))
    )
    (net (code "312") (name "unconnected-(IC1-PT51A-PadD11)") (class "Default")
      (node (ref "IC1") (pin "D11") (pinfunction "PT51A_D11") (pintype "bidirectional"))
    )
    (net (code "313") (name "unconnected-(IC1-PT51B-PadE11)") (class "Default")
      (node (ref "IC1") (pin "E11") (pinfunction "PT51B_E11") (pintype "bidirectional"))
    )
    (net (code "314") (name "unconnected-(IC1-PT56B-PadC12)") (class "Default")
      (node (ref "IC1") (pin "C12") (pinfunction "PT56B_C12") (pintype "bidirectional"))
    )
    (net (code "315") (name "unconnected-(IC1-PT58A-PadD12)") (class "Default")
      (node (ref "IC1") (pin "D12") (pinfunction "PT58A_D12") (pintype "bidirectional"))
    )
    (net (code "316") (name "unconnected-(IC1-PT58B-PadE12)") (class "Default")
      (node (ref "IC1") (pin "E12") (pinfunction "PT58B_E12") (pintype "bidirectional"))
    )
    (net (code "317") (name "unconnected-(IC1-PT60B-PadC13)") (class "Default")
      (node (ref "IC1") (pin "C13") (pinfunction "PT60B_C13") (pintype "bidirectional"))
    )
    (net (code "318") (name "unconnected-(IC1-PT62A-PadD13)") (class "Default")
      (node (ref "IC1") (pin "D13") (pinfunction "PT62A_D13") (pintype "bidirectional"))
    )
    (net (code "319") (name "unconnected-(IC1-PT62B-PadE13)") (class "Default")
      (node (ref "IC1") (pin "E13") (pinfunction "PT62B_E13") (pintype "bidirectional"))
    )
    (net (code "320") (name "unconnected-(J2-SBU1-PadA8)") (class "Default")
      (node (ref "J2") (pin "A8") (pinfunction "SBU1_A8") (pintype "bidirectional"))
    )
    (net (code "321") (name "unconnected-(J2-SBU2-PadB8)") (class "Default")
      (node (ref "J2") (pin "B8") (pinfunction "SBU2_B8") (pintype "bidirectional"))
    )
    (net (code "322") (name "unconnected-(S1-Pad2)") (class "Default")
      (node (ref "S1") (pin "2") (pinfunction "2_2") (pintype "passive"))
    )
    (net (code "323") (name "unconnected-(S1-Pad4)") (class "Default")
      (node (ref "S1") (pin "4") (pinfunction "4_4") (pintype "passive"))
    )
    (net (code "324") (name "unconnected-(U$9-PadIRQ)") (class "Default")
      (node (ref "U$9") (pin "IRQ") (pinfunction "IRQ_IRQ") (pintype "bidirectional"))
    )
    (net (code "325") (name "unconnected-(U4-HOLD-Pad7)") (class "Default")
      (node (ref "U4") (pin "7") (pinfunction "HOLD_7") (pintype "bidirectional"))
    )
    (net (code "326") (name "unconnected-(U4-WP-Pad3)") (class "Default")
      (node (ref "U4") (pin "3") (pinfunction "WP_3") (pintype "bidirectional"))
    )
    (net (code "327") (name "unconnected-(U13-ACBUS0-Pad21)") (class "Default")
      (node (ref "U13") (pin "21") (pinfunction "ACBUS0_21") (pintype "bidirectional"))
    )
    (net (code "328") (name "unconnected-(U13-ACBUS1-Pad25)") (class "Default")
      (node (ref "U13") (pin "25") (pinfunction "ACBUS1_25") (pintype "bidirectional"))
    )
    (net (code "329") (name "unconnected-(U13-ACBUS2-Pad26)") (class "Default")
      (node (ref "U13") (pin "26") (pinfunction "ACBUS2_26") (pintype "bidirectional"))
    )
    (net (code "330") (name "unconnected-(U13-ACBUS3-Pad27)") (class "Default")
      (node (ref "U13") (pin "27") (pinfunction "ACBUS3_27") (pintype "bidirectional"))
    )
    (net (code "331") (name "unconnected-(U13-ACBUS4-Pad28)") (class "Default")
      (node (ref "U13") (pin "28") (pinfunction "ACBUS4_28") (pintype "bidirectional"))
    )
    (net (code "332") (name "unconnected-(U13-ACBUS5-Pad29)") (class "Default")
      (node (ref "U13") (pin "29") (pinfunction "ACBUS5_29") (pintype "bidirectional"))
    )
    (net (code "333") (name "unconnected-(U13-ACBUS6-Pad30)") (class "Default")
      (node (ref "U13") (pin "30") (pinfunction "ACBUS6_30") (pintype "bidirectional"))
    )
    (net (code "334") (name "unconnected-(U13-ACBUS7{slash}PWRSAV#-Pad31)") (class "Default")
      (node (ref "U13") (pin "31") (pinfunction "ACBUS7/PWRSAV#_31") (pintype "bidirectional"))
    )
    (net (code "335") (name "unconnected-(U13-ACBUS8-Pad32)") (class "Default")
      (node (ref "U13") (pin "32") (pinfunction "ACBUS8_32") (pintype "bidirectional"))
    )
    (net (code "336") (name "unconnected-(U13-ACBUS9-Pad33)") (class "Default")
      (node (ref "U13") (pin "33") (pinfunction "ACBUS9_33") (pintype "bidirectional"))
    )
    (net (code "337") (name "unconnected-(U13-ADBUS4-Pad17)") (class "Default")
      (node (ref "U13") (pin "17") (pinfunction "ADBUS4_17") (pintype "bidirectional"))
    )
    (net (code "338") (name "unconnected-(U13-ADBUS5-Pad18)") (class "Default")
      (node (ref "U13") (pin "18") (pinfunction "ADBUS5_18") (pintype "bidirectional"))
    )
    (net (code "339") (name "unconnected-(U13-ADBUS6-Pad19)") (class "Default")
      (node (ref "U13") (pin "19") (pinfunction "ADBUS6_19") (pintype "bidirectional"))
    )
    (net (code "340") (name "unconnected-(U13-ADBUS7-Pad20)") (class "Default")
      (node (ref "U13") (pin "20") (pinfunction "ADBUS7_20") (pintype "bidirectional"))
    )
    (net (code "341") (name "unconnected-(U14-BYPASS-Pad4)") (class "Default")
      (node (ref "U14") (pin "4") (pinfunction "BYPASS_4") (pintype "bidirectional"))
    )
    (net (code "342") (name "unconnected-(U15-INT1{slash}INT-Pad4)") (class "Default")
      (node (ref "U15") (pin "4") (pinfunction "INT1/INT_4") (pintype "output"))
    )
    (net (code "343") (name "unconnected-(U16-DO-Pad1)") (class "Default")
      (node (ref "U16") (pin "1") (pinfunction "DO_1") (pintype "output"))
    )
  )
)
